# 301_PowerGridUSB.net
KiCad netlist of a schematic drawn in Altium Designer
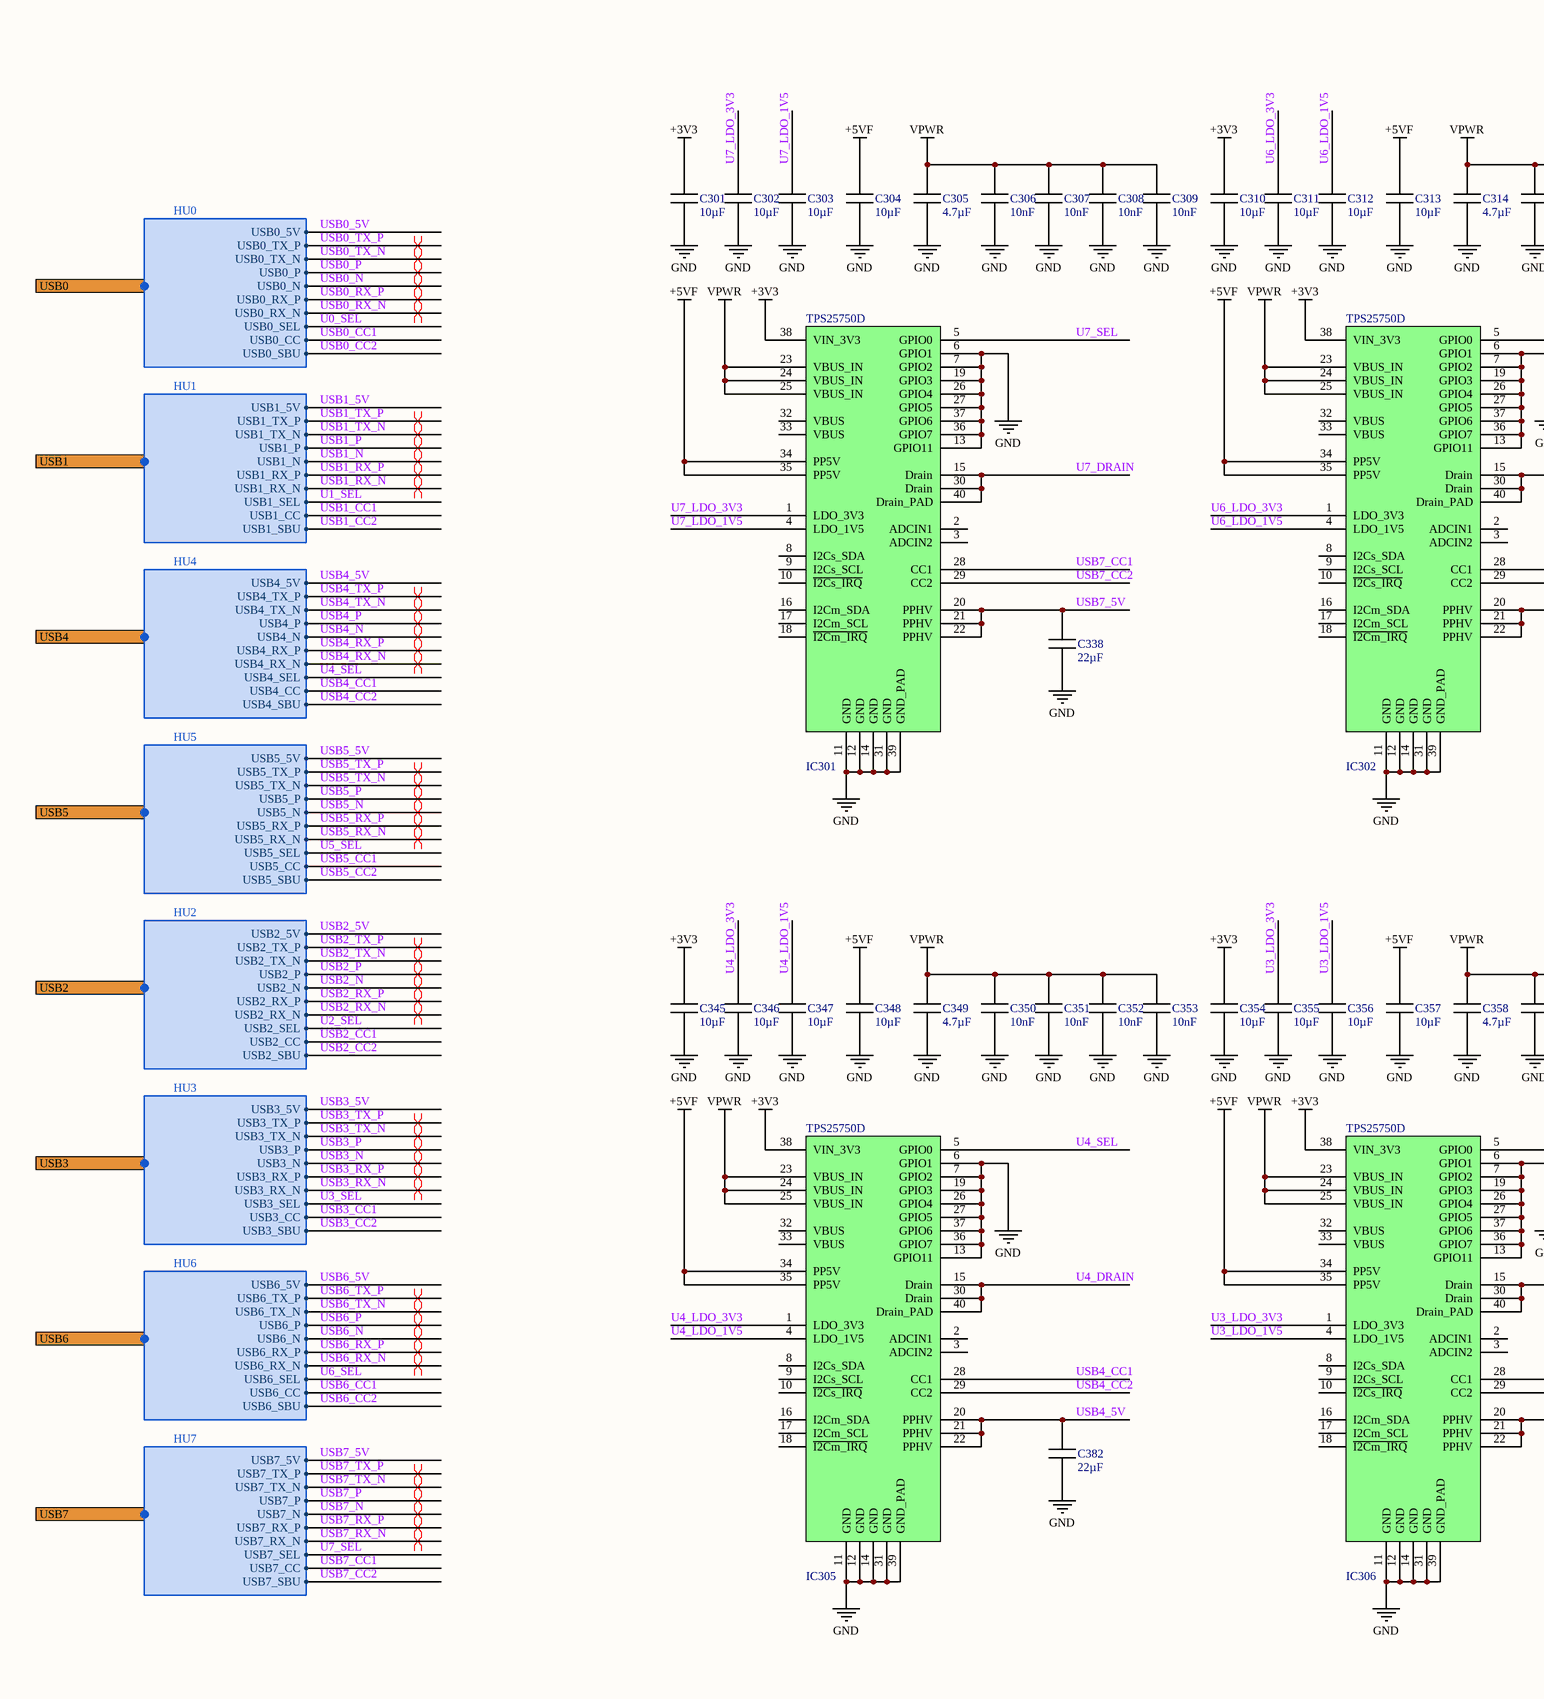
[diagram p0: 301_PowerGridUSB.SchDoc, left]
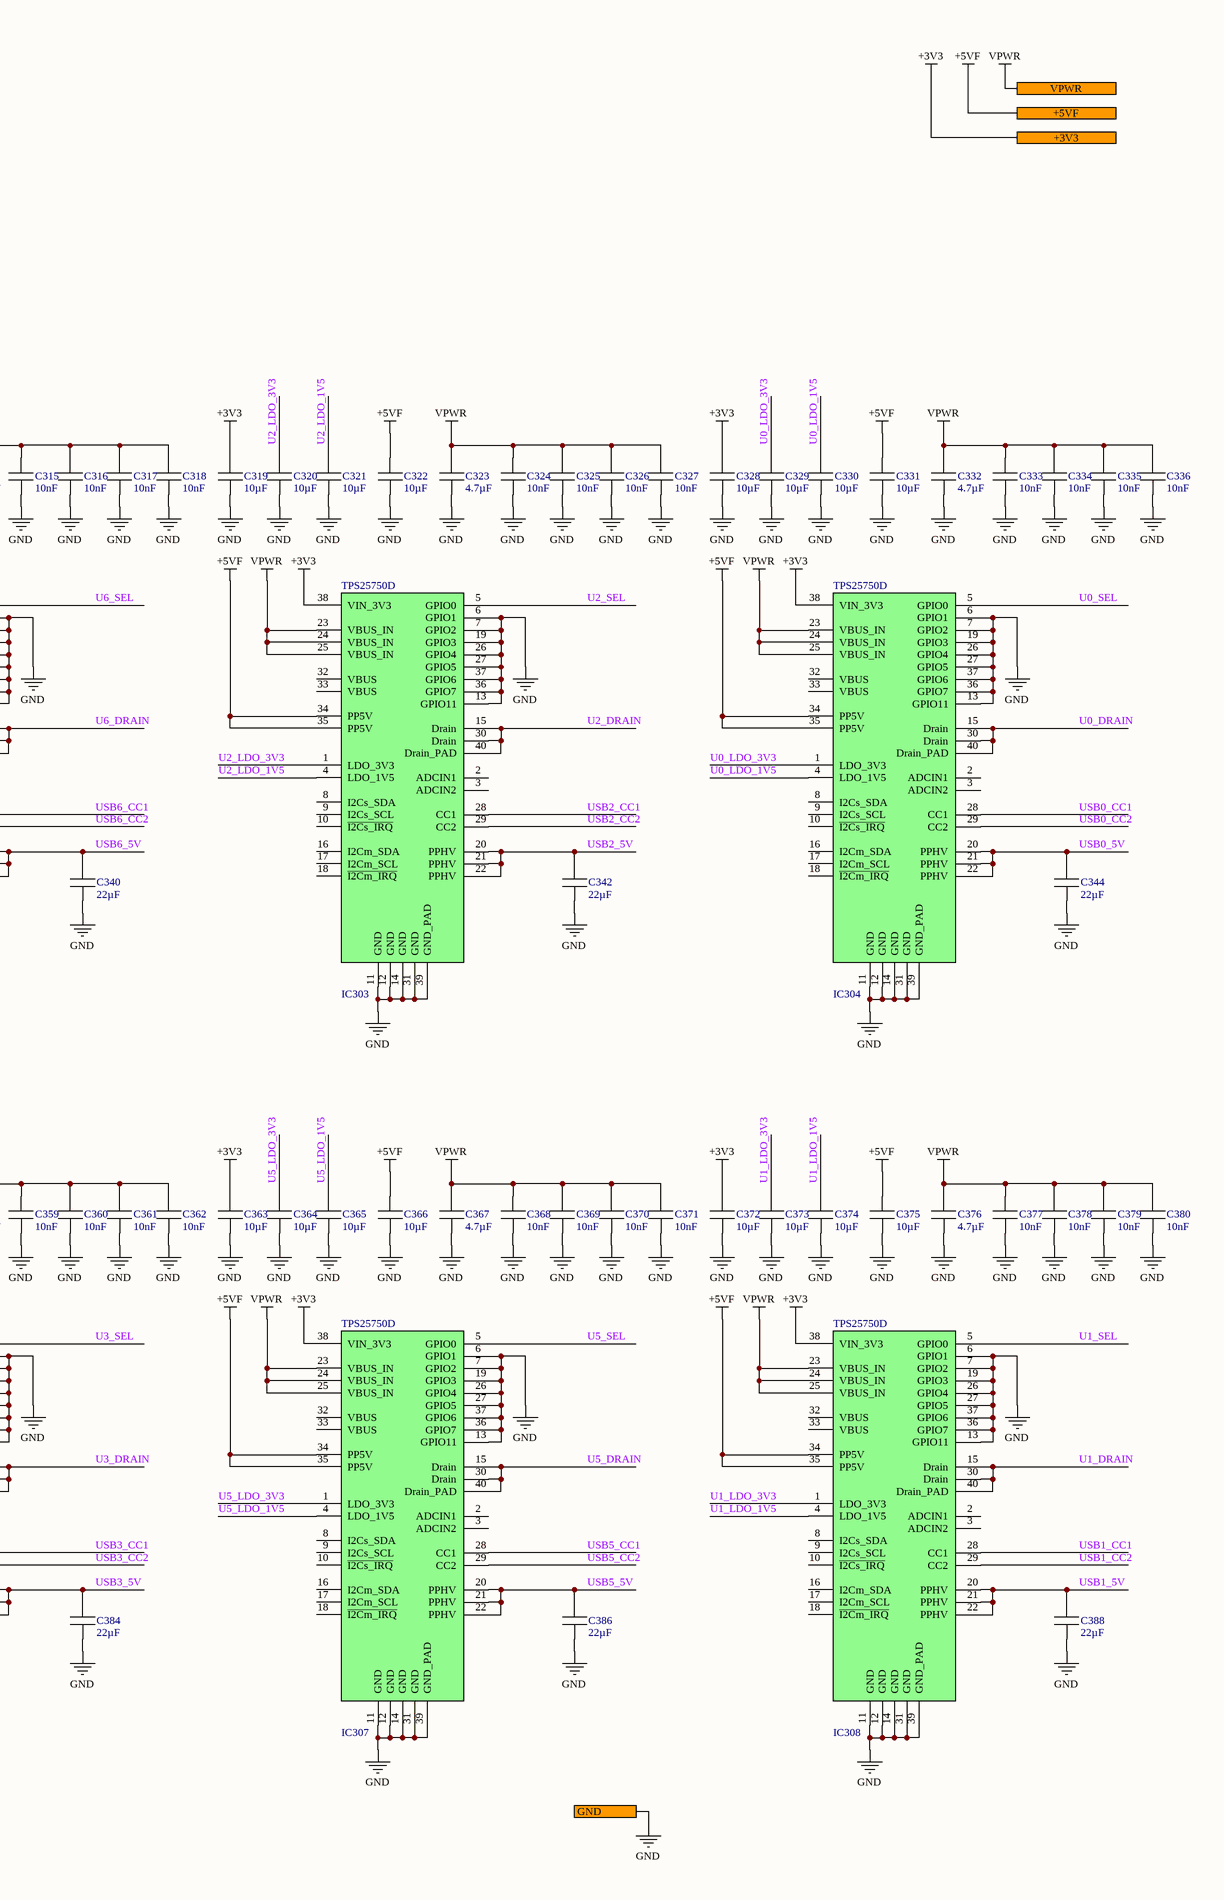
[diagram p1: 301_PowerGridUSB.SchDoc, right]

(export (version "E")
  (design (tool "Eeschema 10.0.6"))
  (components
    (comp (ref "C301")
      (value "10µF")
      (footprint "C0805")
      (description "10µF 16V 10% X5R")
      (fields
        (field (name "REFVAL") "10µF")
        (field (name "PART NUMBER") "CA0001")
        (field (name "MANFACTPART") "GRM21BR61C106KE15L")
      )
      (libsource (lib "GTS_Database") (part "C"))
    )
    (comp (ref "C302")
      (value "10µF")
      (footprint "C0805")
      (description "10µF 16V 10% X5R")
      (fields
        (field (name "REFVAL") "10µF")
        (field (name "PART NUMBER") "CA0001")
        (field (name "MANFACTPART") "GRM21BR61C106KE15L")
      )
      (libsource (lib "GTS_Database") (part "C"))
    )
    (comp (ref "C303")
      (value "10µF")
      (footprint "C0805")
      (description "10µF 16V 10% X5R")
      (fields
        (field (name "REFVAL") "10µF")
        (field (name "PART NUMBER") "CA0001")
        (field (name "MANFACTPART") "GRM21BR61C106KE15L")
      )
      (libsource (lib "GTS_Database") (part "C"))
    )
    (comp (ref "C304")
      (value "10µF")
      (footprint "C0805")
      (description "10µF 16V 10% X5R")
      (fields
        (field (name "REFVAL") "10µF")
        (field (name "PART NUMBER") "CA0001")
        (field (name "MANFACTPART") "GRM21BR61C106KE15L")
      )
      (libsource (lib "GTS_Database") (part "C"))
    )
    (comp (ref "C305")
      (value "4.7µF")
      (footprint "C1210")
      (description "4.7µF 100V 10% X5R")
      (fields
        (field (name "REFVAL") "4.7µF")
        (field (name "PART NUMBER") "CA0038")
        (field (name "MANFACTPART") "HMK325BJ475KM-PE")
      )
      (libsource (lib "GTS_Database") (part "C"))
    )
    (comp (ref "C306")
      (value "10nF")
      (footprint "C0805")
      (description "10nF 50V 10% X7R")
      (fields
        (field (name "REFVAL") "10nF")
        (field (name "PART NUMBER") "CA0021")
        (field (name "MANFACTPART") "C0805C103K5RAC")
      )
      (libsource (lib "GTS_Database") (part "C"))
    )
    (comp (ref "C307")
      (value "10nF")
      (footprint "C0805")
      (description "10nF 50V 10% X7R")
      (fields
        (field (name "REFVAL") "10nF")
        (field (name "PART NUMBER") "CA0021")
        (field (name "MANFACTPART") "C0805C103K5RAC")
      )
      (libsource (lib "GTS_Database") (part "C"))
    )
    (comp (ref "C308")
      (value "10nF")
      (footprint "C0805")
      (description "10nF 50V 10% X7R")
      (fields
        (field (name "REFVAL") "10nF")
        (field (name "PART NUMBER") "CA0021")
        (field (name "MANFACTPART") "C0805C103K5RAC")
      )
      (libsource (lib "GTS_Database") (part "C"))
    )
    (comp (ref "C309")
      (value "10nF")
      (footprint "C0805")
      (description "10nF 50V 10% X7R")
      (fields
        (field (name "REFVAL") "10nF")
        (field (name "PART NUMBER") "CA0021")
        (field (name "MANFACTPART") "C0805C103K5RAC")
      )
      (libsource (lib "GTS_Database") (part "C"))
    )
    (comp (ref "C310")
      (value "10µF")
      (footprint "C0805")
      (description "10µF 16V 10% X5R")
      (fields
        (field (name "REFVAL") "10µF")
        (field (name "PART NUMBER") "CA0001")
        (field (name "MANFACTPART") "GRM21BR61C106KE15L")
      )
      (libsource (lib "GTS_Database") (part "C"))
    )
    (comp (ref "C311")
      (value "10µF")
      (footprint "C0805")
      (description "10µF 16V 10% X5R")
      (fields
        (field (name "REFVAL") "10µF")
        (field (name "PART NUMBER") "CA0001")
        (field (name "MANFACTPART") "GRM21BR61C106KE15L")
      )
      (libsource (lib "GTS_Database") (part "C"))
    )
    (comp (ref "C312")
      (value "10µF")
      (footprint "C0805")
      (description "10µF 16V 10% X5R")
      (fields
        (field (name "REFVAL") "10µF")
        (field (name "PART NUMBER") "CA0001")
        (field (name "MANFACTPART") "GRM21BR61C106KE15L")
      )
      (libsource (lib "GTS_Database") (part "C"))
    )
    (comp (ref "C313")
      (value "10µF")
      (footprint "C0805")
      (description "10µF 16V 10% X5R")
      (fields
        (field (name "REFVAL") "10µF")
        (field (name "PART NUMBER") "CA0001")
        (field (name "MANFACTPART") "GRM21BR61C106KE15L")
      )
      (libsource (lib "GTS_Database") (part "C"))
    )
    (comp (ref "C314")
      (value "4.7µF")
      (footprint "C1210")
      (description "4.7µF 100V 10% X5R")
      (fields
        (field (name "REFVAL") "4.7µF")
        (field (name "PART NUMBER") "CA0038")
        (field (name "MANFACTPART") "HMK325BJ475KM-PE")
      )
      (libsource (lib "GTS_Database") (part "C"))
    )
    (comp (ref "C315")
      (value "10nF")
      (footprint "C0805")
      (description "10nF 50V 10% X7R")
      (fields
        (field (name "REFVAL") "10nF")
        (field (name "PART NUMBER") "CA0021")
        (field (name "MANFACTPART") "C0805C103K5RAC")
      )
      (libsource (lib "GTS_Database") (part "C"))
    )
    (comp (ref "C316")
      (value "10nF")
      (footprint "C0805")
      (description "10nF 50V 10% X7R")
      (fields
        (field (name "REFVAL") "10nF")
        (field (name "PART NUMBER") "CA0021")
        (field (name "MANFACTPART") "C0805C103K5RAC")
      )
      (libsource (lib "GTS_Database") (part "C"))
    )
    (comp (ref "C317")
      (value "10nF")
      (footprint "C0805")
      (description "10nF 50V 10% X7R")
      (fields
        (field (name "REFVAL") "10nF")
        (field (name "PART NUMBER") "CA0021")
        (field (name "MANFACTPART") "C0805C103K5RAC")
      )
      (libsource (lib "GTS_Database") (part "C"))
    )
    (comp (ref "C318")
      (value "10nF")
      (footprint "C0805")
      (description "10nF 50V 10% X7R")
      (fields
        (field (name "REFVAL") "10nF")
        (field (name "PART NUMBER") "CA0021")
        (field (name "MANFACTPART") "C0805C103K5RAC")
      )
      (libsource (lib "GTS_Database") (part "C"))
    )
    (comp (ref "C319")
      (value "10µF")
      (footprint "C0805")
      (description "10µF 16V 10% X5R")
      (fields
        (field (name "REFVAL") "10µF")
        (field (name "PART NUMBER") "CA0001")
        (field (name "MANFACTPART") "GRM21BR61C106KE15L")
      )
      (libsource (lib "GTS_Database") (part "C"))
    )
    (comp (ref "C320")
      (value "10µF")
      (footprint "C0805")
      (description "10µF 16V 10% X5R")
      (fields
        (field (name "REFVAL") "10µF")
        (field (name "PART NUMBER") "CA0001")
        (field (name "MANFACTPART") "GRM21BR61C106KE15L")
      )
      (libsource (lib "GTS_Database") (part "C"))
    )
    (comp (ref "C321")
      (value "10µF")
      (footprint "C0805")
      (description "10µF 16V 10% X5R")
      (fields
        (field (name "REFVAL") "10µF")
        (field (name "PART NUMBER") "CA0001")
        (field (name "MANFACTPART") "GRM21BR61C106KE15L")
      )
      (libsource (lib "GTS_Database") (part "C"))
    )
    (comp (ref "C322")
      (value "10µF")
      (footprint "C0805")
      (description "10µF 16V 10% X5R")
      (fields
        (field (name "REFVAL") "10µF")
        (field (name "PART NUMBER") "CA0001")
        (field (name "MANFACTPART") "GRM21BR61C106KE15L")
      )
      (libsource (lib "GTS_Database") (part "C"))
    )
    (comp (ref "C323")
      (value "4.7µF")
      (footprint "C1210")
      (description "4.7µF 100V 10% X5R")
      (fields
        (field (name "REFVAL") "4.7µF")
        (field (name "PART NUMBER") "CA0038")
        (field (name "MANFACTPART") "HMK325BJ475KM-PE")
      )
      (libsource (lib "GTS_Database") (part "C"))
    )
    (comp (ref "C324")
      (value "10nF")
      (footprint "C0805")
      (description "10nF 50V 10% X7R")
      (fields
        (field (name "REFVAL") "10nF")
        (field (name "PART NUMBER") "CA0021")
        (field (name "MANFACTPART") "C0805C103K5RAC")
      )
      (libsource (lib "GTS_Database") (part "C"))
    )
    (comp (ref "C325")
      (value "10nF")
      (footprint "C0805")
      (description "10nF 50V 10% X7R")
      (fields
        (field (name "REFVAL") "10nF")
        (field (name "PART NUMBER") "CA0021")
        (field (name "MANFACTPART") "C0805C103K5RAC")
      )
      (libsource (lib "GTS_Database") (part "C"))
    )
    (comp (ref "C326")
      (value "10nF")
      (footprint "C0805")
      (description "10nF 50V 10% X7R")
      (fields
        (field (name "REFVAL") "10nF")
        (field (name "PART NUMBER") "CA0021")
        (field (name "MANFACTPART") "C0805C103K5RAC")
      )
      (libsource (lib "GTS_Database") (part "C"))
    )
    (comp (ref "C327")
      (value "10nF")
      (footprint "C0805")
      (description "10nF 50V 10% X7R")
      (fields
        (field (name "REFVAL") "10nF")
        (field (name "PART NUMBER") "CA0021")
        (field (name "MANFACTPART") "C0805C103K5RAC")
      )
      (libsource (lib "GTS_Database") (part "C"))
    )
    (comp (ref "C328")
      (value "10µF")
      (footprint "C0805")
      (description "10µF 16V 10% X5R")
      (fields
        (field (name "REFVAL") "10µF")
        (field (name "PART NUMBER") "CA0001")
        (field (name "MANFACTPART") "GRM21BR61C106KE15L")
      )
      (libsource (lib "GTS_Database") (part "C"))
    )
    (comp (ref "C329")
      (value "10µF")
      (footprint "C0805")
      (description "10µF 16V 10% X5R")
      (fields
        (field (name "REFVAL") "10µF")
        (field (name "PART NUMBER") "CA0001")
        (field (name "MANFACTPART") "GRM21BR61C106KE15L")
      )
      (libsource (lib "GTS_Database") (part "C"))
    )
    (comp (ref "C330")
      (value "10µF")
      (footprint "C0805")
      (description "10µF 16V 10% X5R")
      (fields
        (field (name "REFVAL") "10µF")
        (field (name "PART NUMBER") "CA0001")
        (field (name "MANFACTPART") "GRM21BR61C106KE15L")
      )
      (libsource (lib "GTS_Database") (part "C"))
    )
    (comp (ref "C331")
      (value "10µF")
      (footprint "C0805")
      (description "10µF 16V 10% X5R")
      (fields
        (field (name "REFVAL") "10µF")
        (field (name "PART NUMBER") "CA0001")
        (field (name "MANFACTPART") "GRM21BR61C106KE15L")
      )
      (libsource (lib "GTS_Database") (part "C"))
    )
    (comp (ref "C332")
      (value "4.7µF")
      (footprint "C1210")
      (description "4.7µF 100V 10% X5R")
      (fields
        (field (name "REFVAL") "4.7µF")
        (field (name "PART NUMBER") "CA0038")
        (field (name "MANFACTPART") "HMK325BJ475KM-PE")
      )
      (libsource (lib "GTS_Database") (part "C"))
    )
    (comp (ref "C333")
      (value "10nF")
      (footprint "C0805")
      (description "10nF 50V 10% X7R")
      (fields
        (field (name "REFVAL") "10nF")
        (field (name "PART NUMBER") "CA0021")
        (field (name "MANFACTPART") "C0805C103K5RAC")
      )
      (libsource (lib "GTS_Database") (part "C"))
    )
    (comp (ref "C334")
      (value "10nF")
      (footprint "C0805")
      (description "10nF 50V 10% X7R")
      (fields
        (field (name "REFVAL") "10nF")
        (field (name "PART NUMBER") "CA0021")
        (field (name "MANFACTPART") "C0805C103K5RAC")
      )
      (libsource (lib "GTS_Database") (part "C"))
    )
    (comp (ref "C335")
      (value "10nF")
      (footprint "C0805")
      (description "10nF 50V 10% X7R")
      (fields
        (field (name "REFVAL") "10nF")
        (field (name "PART NUMBER") "CA0021")
        (field (name "MANFACTPART") "C0805C103K5RAC")
      )
      (libsource (lib "GTS_Database") (part "C"))
    )
    (comp (ref "C336")
      (value "10nF")
      (footprint "C0805")
      (description "10nF 50V 10% X7R")
      (fields
        (field (name "REFVAL") "10nF")
        (field (name "PART NUMBER") "CA0021")
        (field (name "MANFACTPART") "C0805C103K5RAC")
      )
      (libsource (lib "GTS_Database") (part "C"))
    )
    (comp (ref "C338")
      (value "22µF")
      (footprint "C2220")
      (description "22µF 63V 20% X7R")
      (fields
        (field (name "REFVAL") "22µF")
        (field (name "PART NUMBER") "CA0051")
        (field (name "MANFACTPART") "KRM55WR71J226MH01K")
      )
      (libsource (lib "GTS_Database") (part "C"))
    )
    (comp (ref "C340")
      (value "22µF")
      (footprint "C2220")
      (description "22µF 63V 20% X7R")
      (fields
        (field (name "REFVAL") "22µF")
        (field (name "PART NUMBER") "CA0051")
        (field (name "MANFACTPART") "KRM55WR71J226MH01K")
      )
      (libsource (lib "GTS_Database") (part "C"))
    )
    (comp (ref "C342")
      (value "22µF")
      (footprint "C2220")
      (description "22µF 63V 20% X7R")
      (fields
        (field (name "REFVAL") "22µF")
        (field (name "PART NUMBER") "CA0051")
        (field (name "MANFACTPART") "KRM55WR71J226MH01K")
      )
      (libsource (lib "GTS_Database") (part "C"))
    )
    (comp (ref "C344")
      (value "22µF")
      (footprint "C2220")
      (description "22µF 63V 20% X7R")
      (fields
        (field (name "REFVAL") "22µF")
        (field (name "PART NUMBER") "CA0051")
        (field (name "MANFACTPART") "KRM55WR71J226MH01K")
      )
      (libsource (lib "GTS_Database") (part "C"))
    )
    (comp (ref "C345")
      (value "10µF")
      (footprint "C0805")
      (description "10µF 16V 10% X5R")
      (fields
        (field (name "REFVAL") "10µF")
        (field (name "PART NUMBER") "CA0001")
        (field (name "MANFACTPART") "GRM21BR61C106KE15L")
      )
      (libsource (lib "GTS_Database") (part "C"))
    )
    (comp (ref "C346")
      (value "10µF")
      (footprint "C0805")
      (description "10µF 16V 10% X5R")
      (fields
        (field (name "REFVAL") "10µF")
        (field (name "PART NUMBER") "CA0001")
        (field (name "MANFACTPART") "GRM21BR61C106KE15L")
      )
      (libsource (lib "GTS_Database") (part "C"))
    )
    (comp (ref "C347")
      (value "10µF")
      (footprint "C0805")
      (description "10µF 16V 10% X5R")
      (fields
        (field (name "REFVAL") "10µF")
        (field (name "PART NUMBER") "CA0001")
        (field (name "MANFACTPART") "GRM21BR61C106KE15L")
      )
      (libsource (lib "GTS_Database") (part "C"))
    )
    (comp (ref "C348")
      (value "10µF")
      (footprint "C0805")
      (description "10µF 16V 10% X5R")
      (fields
        (field (name "REFVAL") "10µF")
        (field (name "PART NUMBER") "CA0001")
        (field (name "MANFACTPART") "GRM21BR61C106KE15L")
      )
      (libsource (lib "GTS_Database") (part "C"))
    )
    (comp (ref "C349")
      (value "4.7µF")
      (footprint "C1210")
      (description "4.7µF 100V 10% X5R")
      (fields
        (field (name "REFVAL") "4.7µF")
        (field (name "PART NUMBER") "CA0038")
        (field (name "MANFACTPART") "HMK325BJ475KM-PE")
      )
      (libsource (lib "GTS_Database") (part "C"))
    )
    (comp (ref "C350")
      (value "10nF")
      (footprint "C0805")
      (description "10nF 50V 10% X7R")
      (fields
        (field (name "REFVAL") "10nF")
        (field (name "PART NUMBER") "CA0021")
        (field (name "MANFACTPART") "C0805C103K5RAC")
      )
      (libsource (lib "GTS_Database") (part "C"))
    )
    (comp (ref "C351")
      (value "10nF")
      (footprint "C0805")
      (description "10nF 50V 10% X7R")
      (fields
        (field (name "REFVAL") "10nF")
        (field (name "PART NUMBER") "CA0021")
        (field (name "MANFACTPART") "C0805C103K5RAC")
      )
      (libsource (lib "GTS_Database") (part "C"))
    )
    (comp (ref "C352")
      (value "10nF")
      (footprint "C0805")
      (description "10nF 50V 10% X7R")
      (fields
        (field (name "REFVAL") "10nF")
        (field (name "PART NUMBER") "CA0021")
        (field (name "MANFACTPART") "C0805C103K5RAC")
      )
      (libsource (lib "GTS_Database") (part "C"))
    )
    (comp (ref "C353")
      (value "10nF")
      (footprint "C0805")
      (description "10nF 50V 10% X7R")
      (fields
        (field (name "REFVAL") "10nF")
        (field (name "PART NUMBER") "CA0021")
        (field (name "MANFACTPART") "C0805C103K5RAC")
      )
      (libsource (lib "GTS_Database") (part "C"))
    )
    (comp (ref "C354")
      (value "10µF")
      (footprint "C0805")
      (description "10µF 16V 10% X5R")
      (fields
        (field (name "REFVAL") "10µF")
        (field (name "PART NUMBER") "CA0001")
        (field (name "MANFACTPART") "GRM21BR61C106KE15L")
      )
      (libsource (lib "GTS_Database") (part "C"))
    )
    (comp (ref "C355")
      (value "10µF")
      (footprint "C0805")
      (description "10µF 16V 10% X5R")
      (fields
        (field (name "REFVAL") "10µF")
        (field (name "PART NUMBER") "CA0001")
        (field (name "MANFACTPART") "GRM21BR61C106KE15L")
      )
      (libsource (lib "GTS_Database") (part "C"))
    )
    (comp (ref "C356")
      (value "10µF")
      (footprint "C0805")
      (description "10µF 16V 10% X5R")
      (fields
        (field (name "REFVAL") "10µF")
        (field (name "PART NUMBER") "CA0001")
        (field (name "MANFACTPART") "GRM21BR61C106KE15L")
      )
      (libsource (lib "GTS_Database") (part "C"))
    )
    (comp (ref "C357")
      (value "10µF")
      (footprint "C0805")
      (description "10µF 16V 10% X5R")
      (fields
        (field (name "REFVAL") "10µF")
        (field (name "PART NUMBER") "CA0001")
        (field (name "MANFACTPART") "GRM21BR61C106KE15L")
      )
      (libsource (lib "GTS_Database") (part "C"))
    )
    (comp (ref "C358")
      (value "4.7µF")
      (footprint "C1210")
      (description "4.7µF 100V 10% X5R")
      (fields
        (field (name "REFVAL") "4.7µF")
        (field (name "PART NUMBER") "CA0038")
        (field (name "MANFACTPART") "HMK325BJ475KM-PE")
      )
      (libsource (lib "GTS_Database") (part "C"))
    )
    (comp (ref "C359")
      (value "10nF")
      (footprint "C0805")
      (description "10nF 50V 10% X7R")
      (fields
        (field (name "REFVAL") "10nF")
        (field (name "PART NUMBER") "CA0021")
        (field (name "MANFACTPART") "C0805C103K5RAC")
      )
      (libsource (lib "GTS_Database") (part "C"))
    )
    (comp (ref "C360")
      (value "10nF")
      (footprint "C0805")
      (description "10nF 50V 10% X7R")
      (fields
        (field (name "REFVAL") "10nF")
        (field (name "PART NUMBER") "CA0021")
        (field (name "MANFACTPART") "C0805C103K5RAC")
      )
      (libsource (lib "GTS_Database") (part "C"))
    )
    (comp (ref "C361")
      (value "10nF")
      (footprint "C0805")
      (description "10nF 50V 10% X7R")
      (fields
        (field (name "REFVAL") "10nF")
        (field (name "PART NUMBER") "CA0021")
        (field (name "MANFACTPART") "C0805C103K5RAC")
      )
      (libsource (lib "GTS_Database") (part "C"))
    )
    (comp (ref "C362")
      (value "10nF")
      (footprint "C0805")
      (description "10nF 50V 10% X7R")
      (fields
        (field (name "REFVAL") "10nF")
        (field (name "PART NUMBER") "CA0021")
        (field (name "MANFACTPART") "C0805C103K5RAC")
      )
      (libsource (lib "GTS_Database") (part "C"))
    )
    (comp (ref "C363")
      (value "10µF")
      (footprint "C0805")
      (description "10µF 16V 10% X5R")
      (fields
        (field (name "REFVAL") "10µF")
        (field (name "PART NUMBER") "CA0001")
        (field (name "MANFACTPART") "GRM21BR61C106KE15L")
      )
      (libsource (lib "GTS_Database") (part "C"))
    )
    (comp (ref "C364")
      (value "10µF")
      (footprint "C0805")
      (description "10µF 16V 10% X5R")
      (fields
        (field (name "REFVAL") "10µF")
        (field (name "PART NUMBER") "CA0001")
        (field (name "MANFACTPART") "GRM21BR61C106KE15L")
      )
      (libsource (lib "GTS_Database") (part "C"))
    )
    (comp (ref "C365")
      (value "10µF")
      (footprint "C0805")
      (description "10µF 16V 10% X5R")
      (fields
        (field (name "REFVAL") "10µF")
        (field (name "PART NUMBER") "CA0001")
        (field (name "MANFACTPART") "GRM21BR61C106KE15L")
      )
      (libsource (lib "GTS_Database") (part "C"))
    )
    (comp (ref "C366")
      (value "10µF")
      (footprint "C0805")
      (description "10µF 16V 10% X5R")
      (fields
        (field (name "REFVAL") "10µF")
        (field (name "PART NUMBER") "CA0001")
        (field (name "MANFACTPART") "GRM21BR61C106KE15L")
      )
      (libsource (lib "GTS_Database") (part "C"))
    )
    (comp (ref "C367")
      (value "4.7µF")
      (footprint "C1210")
      (description "4.7µF 100V 10% X5R")
      (fields
        (field (name "REFVAL") "4.7µF")
        (field (name "PART NUMBER") "CA0038")
        (field (name "MANFACTPART") "HMK325BJ475KM-PE")
      )
      (libsource (lib "GTS_Database") (part "C"))
    )
    (comp (ref "C368")
      (value "10nF")
      (footprint "C0805")
      (description "10nF 50V 10% X7R")
      (fields
        (field (name "REFVAL") "10nF")
        (field (name "PART NUMBER") "CA0021")
        (field (name "MANFACTPART") "C0805C103K5RAC")
      )
      (libsource (lib "GTS_Database") (part "C"))
    )
    (comp (ref "C369")
      (value "10nF")
      (footprint "C0805")
      (description "10nF 50V 10% X7R")
      (fields
        (field (name "REFVAL") "10nF")
        (field (name "PART NUMBER") "CA0021")
        (field (name "MANFACTPART") "C0805C103K5RAC")
      )
      (libsource (lib "GTS_Database") (part "C"))
    )
    (comp (ref "C370")
      (value "10nF")
      (footprint "C0805")
      (description "10nF 50V 10% X7R")
      (fields
        (field (name "REFVAL") "10nF")
        (field (name "PART NUMBER") "CA0021")
        (field (name "MANFACTPART") "C0805C103K5RAC")
      )
      (libsource (lib "GTS_Database") (part "C"))
    )
    (comp (ref "C371")
      (value "10nF")
      (footprint "C0805")
      (description "10nF 50V 10% X7R")
      (fields
        (field (name "REFVAL") "10nF")
        (field (name "PART NUMBER") "CA0021")
        (field (name "MANFACTPART") "C0805C103K5RAC")
      )
      (libsource (lib "GTS_Database") (part "C"))
    )
    (comp (ref "C372")
      (value "10µF")
      (footprint "C0805")
      (description "10µF 16V 10% X5R")
      (fields
        (field (name "REFVAL") "10µF")
        (field (name "PART NUMBER") "CA0001")
        (field (name "MANFACTPART") "GRM21BR61C106KE15L")
      )
      (libsource (lib "GTS_Database") (part "C"))
    )
    (comp (ref "C373")
      (value "10µF")
      (footprint "C0805")
      (description "10µF 16V 10% X5R")
      (fields
        (field (name "REFVAL") "10µF")
        (field (name "PART NUMBER") "CA0001")
        (field (name "MANFACTPART") "GRM21BR61C106KE15L")
      )
      (libsource (lib "GTS_Database") (part "C"))
    )
    (comp (ref "C374")
      (value "10µF")
      (footprint "C0805")
      (description "10µF 16V 10% X5R")
      (fields
        (field (name "REFVAL") "10µF")
        (field (name "PART NUMBER") "CA0001")
        (field (name "MANFACTPART") "GRM21BR61C106KE15L")
      )
      (libsource (lib "GTS_Database") (part "C"))
    )
    (comp (ref "C375")
      (value "10µF")
      (footprint "C0805")
      (description "10µF 16V 10% X5R")
      (fields
        (field (name "REFVAL") "10µF")
        (field (name "PART NUMBER") "CA0001")
        (field (name "MANFACTPART") "GRM21BR61C106KE15L")
      )
      (libsource (lib "GTS_Database") (part "C"))
    )
    (comp (ref "C376")
      (value "4.7µF")
      (footprint "C1210")
      (description "4.7µF 100V 10% X5R")
      (fields
        (field (name "REFVAL") "4.7µF")
        (field (name "PART NUMBER") "CA0038")
        (field (name "MANFACTPART") "HMK325BJ475KM-PE")
      )
      (libsource (lib "GTS_Database") (part "C"))
    )
    (comp (ref "C377")
      (value "10nF")
      (footprint "C0805")
      (description "10nF 50V 10% X7R")
      (fields
        (field (name "REFVAL") "10nF")
        (field (name "PART NUMBER") "CA0021")
        (field (name "MANFACTPART") "C0805C103K5RAC")
      )
      (libsource (lib "GTS_Database") (part "C"))
    )
    (comp (ref "C378")
      (value "10nF")
      (footprint "C0805")
      (description "10nF 50V 10% X7R")
      (fields
        (field (name "REFVAL") "10nF")
        (field (name "PART NUMBER") "CA0021")
        (field (name "MANFACTPART") "C0805C103K5RAC")
      )
      (libsource (lib "GTS_Database") (part "C"))
    )
    (comp (ref "C379")
      (value "10nF")
      (footprint "C0805")
      (description "10nF 50V 10% X7R")
      (fields
        (field (name "REFVAL") "10nF")
        (field (name "PART NUMBER") "CA0021")
        (field (name "MANFACTPART") "C0805C103K5RAC")
      )
      (libsource (lib "GTS_Database") (part "C"))
    )
    (comp (ref "C380")
      (value "10nF")
      (footprint "C0805")
      (description "10nF 50V 10% X7R")
      (fields
        (field (name "REFVAL") "10nF")
        (field (name "PART NUMBER") "CA0021")
        (field (name "MANFACTPART") "C0805C103K5RAC")
      )
      (libsource (lib "GTS_Database") (part "C"))
    )
    (comp (ref "C382")
      (value "22µF")
      (footprint "C2220")
      (description "22µF 63V 20% X7R")
      (fields
        (field (name "REFVAL") "22µF")
        (field (name "PART NUMBER") "CA0051")
        (field (name "MANFACTPART") "KRM55WR71J226MH01K")
      )
      (libsource (lib "GTS_Database") (part "C"))
    )
    (comp (ref "C384")
      (value "22µF")
      (footprint "C2220")
      (description "22µF 63V 20% X7R")
      (fields
        (field (name "REFVAL") "22µF")
        (field (name "PART NUMBER") "CA0051")
        (field (name "MANFACTPART") "KRM55WR71J226MH01K")
      )
      (libsource (lib "GTS_Database") (part "C"))
    )
    (comp (ref "C386")
      (value "22µF")
      (footprint "C2220")
      (description "22µF 63V 20% X7R")
      (fields
        (field (name "REFVAL") "22µF")
        (field (name "PART NUMBER") "CA0051")
        (field (name "MANFACTPART") "KRM55WR71J226MH01K")
      )
      (libsource (lib "GTS_Database") (part "C"))
    )
    (comp (ref "C388")
      (value "22µF")
      (footprint "C2220")
      (description "22µF 63V 20% X7R")
      (fields
        (field (name "REFVAL") "22µF")
        (field (name "PART NUMBER") "CA0051")
        (field (name "MANFACTPART") "KRM55WR71J226MH01K")
      )
      (libsource (lib "GTS_Database") (part "C"))
    )
    (comp (ref "IC301")
      (value "TPS25750D")
      (footprint "QFNRJK-38")
      (description "USB Type-C and USB PD Controller with Integrated Power Switches Optimized for Power Applications")
      (fields (field (name "REFVAL") "TPS25750D") (field (name "PART NUMBER") "IC0041"))
      (libsource (lib "GTS_Database") (part "TPS25750D"))
    )
    (comp (ref "IC302")
      (value "TPS25750D")
      (footprint "QFNRJK-38")
      (description "USB Type-C and USB PD Controller with Integrated Power Switches Optimized for Power Applications")
      (fields (field (name "REFVAL") "TPS25750D") (field (name "PART NUMBER") "IC0041"))
      (libsource (lib "GTS_Database") (part "TPS25750D"))
    )
    (comp (ref "IC303")
      (value "TPS25750D")
      (footprint "QFNRJK-38")
      (description "USB Type-C and USB PD Controller with Integrated Power Switches Optimized for Power Applications")
      (fields (field (name "REFVAL") "TPS25750D") (field (name "PART NUMBER") "IC0041"))
      (libsource (lib "GTS_Database") (part "TPS25750D"))
    )
    (comp (ref "IC304")
      (value "TPS25750D")
      (footprint "QFNRJK-38")
      (description "USB Type-C and USB PD Controller with Integrated Power Switches Optimized for Power Applications")
      (fields (field (name "REFVAL") "TPS25750D") (field (name "PART NUMBER") "IC0041"))
      (libsource (lib "GTS_Database") (part "TPS25750D"))
    )
    (comp (ref "IC305")
      (value "TPS25750D")
      (footprint "QFNRJK-38")
      (description "USB Type-C and USB PD Controller with Integrated Power Switches Optimized for Power Applications")
      (fields (field (name "REFVAL") "TPS25750D") (field (name "PART NUMBER") "IC0041"))
      (libsource (lib "GTS_Database") (part "TPS25750D"))
    )
    (comp (ref "IC306")
      (value "TPS25750D")
      (footprint "QFNRJK-38")
      (description "USB Type-C and USB PD Controller with Integrated Power Switches Optimized for Power Applications")
      (fields (field (name "REFVAL") "TPS25750D") (field (name "PART NUMBER") "IC0041"))
      (libsource (lib "GTS_Database") (part "TPS25750D"))
    )
    (comp (ref "IC307")
      (value "TPS25750D")
      (footprint "QFNRJK-38")
      (description "USB Type-C and USB PD Controller with Integrated Power Switches Optimized for Power Applications")
      (fields (field (name "REFVAL") "TPS25750D") (field (name "PART NUMBER") "IC0041"))
      (libsource (lib "GTS_Database") (part "TPS25750D"))
    )
    (comp (ref "IC308")
      (value "TPS25750D")
      (footprint "QFNRJK-38")
      (description "USB Type-C and USB PD Controller with Integrated Power Switches Optimized for Power Applications")
      (fields (field (name "REFVAL") "TPS25750D") (field (name "PART NUMBER") "IC0041"))
      (libsource (lib "GTS_Database") (part "TPS25750D"))
    )
  )
  (nets
    (net (code "9") (name "+3V3") (class "Default")
      (node (ref "C301") (pin "1") (pinfunction "1_1") (pintype "passive"))
      (node (ref "C310") (pin "1") (pinfunction "1_1") (pintype "passive"))
      (node (ref "C319") (pin "1") (pinfunction "1_1") (pintype "passive"))
      (node (ref "C328") (pin "1") (pinfunction "1_1") (pintype "passive"))
      (node (ref "C345") (pin "1") (pinfunction "1_1") (pintype "passive"))
      (node (ref "C354") (pin "1") (pinfunction "1_1") (pintype "passive"))
      (node (ref "C363") (pin "1") (pinfunction "1_1") (pintype "passive"))
      (node (ref "C372") (pin "1") (pinfunction "1_1") (pintype "passive"))
      (node (ref "IC301") (pin "38") (pinfunction "VIN_3V3_38") (pintype "passive"))
      (node (ref "IC302") (pin "38") (pinfunction "VIN_3V3_38") (pintype "passive"))
      (node (ref "IC303") (pin "38") (pinfunction "VIN_3V3_38") (pintype "passive"))
      (node (ref "IC304") (pin "38") (pinfunction "VIN_3V3_38") (pintype "passive"))
      (node (ref "IC305") (pin "38") (pinfunction "VIN_3V3_38") (pintype "passive"))
      (node (ref "IC306") (pin "38") (pinfunction "VIN_3V3_38") (pintype "passive"))
      (node (ref "IC307") (pin "38") (pinfunction "VIN_3V3_38") (pintype "passive"))
      (node (ref "IC308") (pin "38") (pinfunction "VIN_3V3_38") (pintype "passive"))
    )
    (net (code "10") (name "+5VF") (class "Default")
      (node (ref "C304") (pin "1") (pinfunction "1_1") (pintype "passive"))
      (node (ref "C313") (pin "1") (pinfunction "1_1") (pintype "passive"))
      (node (ref "C322") (pin "1") (pinfunction "1_1") (pintype "passive"))
      (node (ref "C331") (pin "1") (pinfunction "1_1") (pintype "passive"))
      (node (ref "C348") (pin "1") (pinfunction "1_1") (pintype "passive"))
      (node (ref "C357") (pin "1") (pinfunction "1_1") (pintype "passive"))
      (node (ref "C366") (pin "1") (pinfunction "1_1") (pintype "passive"))
      (node (ref "C375") (pin "1") (pinfunction "1_1") (pintype "passive"))
      (node (ref "IC301") (pin "34") (pinfunction "PP5V_34") (pintype "passive"))
      (node (ref "IC301") (pin "35") (pinfunction "PP5V_35") (pintype "passive"))
      (node (ref "IC302") (pin "34") (pinfunction "PP5V_34") (pintype "passive"))
      (node (ref "IC302") (pin "35") (pinfunction "PP5V_35") (pintype "passive"))
      (node (ref "IC303") (pin "34") (pinfunction "PP5V_34") (pintype "passive"))
      (node (ref "IC303") (pin "35") (pinfunction "PP5V_35") (pintype "passive"))
      (node (ref "IC304") (pin "34") (pinfunction "PP5V_34") (pintype "passive"))
      (node (ref "IC304") (pin "35") (pinfunction "PP5V_35") (pintype "passive"))
      (node (ref "IC305") (pin "34") (pinfunction "PP5V_34") (pintype "passive"))
      (node (ref "IC305") (pin "35") (pinfunction "PP5V_35") (pintype "passive"))
      (node (ref "IC306") (pin "34") (pinfunction "PP5V_34") (pintype "passive"))
      (node (ref "IC306") (pin "35") (pinfunction "PP5V_35") (pintype "passive"))
      (node (ref "IC307") (pin "34") (pinfunction "PP5V_34") (pintype "passive"))
      (node (ref "IC307") (pin "35") (pinfunction "PP5V_35") (pintype "passive"))
      (node (ref "IC308") (pin "34") (pinfunction "PP5V_34") (pintype "passive"))
      (node (ref "IC308") (pin "35") (pinfunction "PP5V_35") (pintype "passive"))
    )
    (net (code "11") (name "/U0_DRAIN") (class "Default")
      (node (ref "IC304") (pin "15") (pinfunction "Drain_15") (pintype "passive"))
      (node (ref "IC304") (pin "30") (pinfunction "Drain_30") (pintype "passive"))
      (node (ref "IC304") (pin "40") (pinfunction "Drain_PAD_40") (pintype "passive"))
    )
    (net (code "12") (name "/U0_LDO_1V5") (class "Default")
      (node (ref "C330") (pin "1") (pinfunction "1_1") (pintype "passive"))
      (node (ref "IC304") (pin "4") (pinfunction "LDO_1V5_4") (pintype "passive"))
    )
    (net (code "13") (name "/U0_LDO_3V3") (class "Default")
      (node (ref "C329") (pin "1") (pinfunction "1_1") (pintype "passive"))
      (node (ref "IC304") (pin "1") (pinfunction "LDO_3V3_1") (pintype "passive"))
    )
    (net (code "14") (name "/U0_SEL") (class "Default")
      (node (ref "IC304") (pin "5") (pinfunction "GPIO0_5") (pintype "passive"))
    )
    (net (code "15") (name "/U1_DRAIN") (class "Default")
      (node (ref "IC308") (pin "15") (pinfunction "Drain_15") (pintype "passive"))
      (node (ref "IC308") (pin "30") (pinfunction "Drain_30") (pintype "passive"))
      (node (ref "IC308") (pin "40") (pinfunction "Drain_PAD_40") (pintype "passive"))
    )
    (net (code "16") (name "/U1_LDO_1V5") (class "Default")
      (node (ref "C374") (pin "1") (pinfunction "1_1") (pintype "passive"))
      (node (ref "IC308") (pin "4") (pinfunction "LDO_1V5_4") (pintype "passive"))
    )
    (net (code "17") (name "/U1_LDO_3V3") (class "Default")
      (node (ref "C373") (pin "1") (pinfunction "1_1") (pintype "passive"))
      (node (ref "IC308") (pin "1") (pinfunction "LDO_3V3_1") (pintype "passive"))
    )
    (net (code "18") (name "/U1_SEL") (class "Default")
      (node (ref "IC308") (pin "5") (pinfunction "GPIO0_5") (pintype "passive"))
    )
    (net (code "19") (name "/U2_DRAIN") (class "Default")
      (node (ref "IC303") (pin "15") (pinfunction "Drain_15") (pintype "passive"))
      (node (ref "IC303") (pin "30") (pinfunction "Drain_30") (pintype "passive"))
      (node (ref "IC303") (pin "40") (pinfunction "Drain_PAD_40") (pintype "passive"))
    )
    (net (code "20") (name "/U2_LDO_1V5") (class "Default")
      (node (ref "C321") (pin "1") (pinfunction "1_1") (pintype "passive"))
      (node (ref "IC303") (pin "4") (pinfunction "LDO_1V5_4") (pintype "passive"))
    )
    (net (code "21") (name "/U2_LDO_3V3") (class "Default")
      (node (ref "C320") (pin "1") (pinfunction "1_1") (pintype "passive"))
      (node (ref "IC303") (pin "1") (pinfunction "LDO_3V3_1") (pintype "passive"))
    )
    (net (code "22") (name "/U2_SEL") (class "Default")
      (node (ref "IC303") (pin "5") (pinfunction "GPIO0_5") (pintype "passive"))
    )
    (net (code "23") (name "/U3_DRAIN") (class "Default")
      (node (ref "IC306") (pin "15") (pinfunction "Drain_15") (pintype "passive"))
      (node (ref "IC306") (pin "30") (pinfunction "Drain_30") (pintype "passive"))
      (node (ref "IC306") (pin "40") (pinfunction "Drain_PAD_40") (pintype "passive"))
    )
    (net (code "24") (name "/U3_LDO_1V5") (class "Default")
      (node (ref "C356") (pin "1") (pinfunction "1_1") (pintype "passive"))
      (node (ref "IC306") (pin "4") (pinfunction "LDO_1V5_4") (pintype "passive"))
    )
    (net (code "25") (name "/U3_LDO_3V3") (class "Default")
      (node (ref "C355") (pin "1") (pinfunction "1_1") (pintype "passive"))
      (node (ref "IC306") (pin "1") (pinfunction "LDO_3V3_1") (pintype "passive"))
    )
    (net (code "26") (name "/U3_SEL") (class "Default")
      (node (ref "IC306") (pin "5") (pinfunction "GPIO0_5") (pintype "passive"))
    )
    (net (code "27") (name "/U4_DRAIN") (class "Default")
      (node (ref "IC305") (pin "15") (pinfunction "Drain_15") (pintype "passive"))
      (node (ref "IC305") (pin "30") (pinfunction "Drain_30") (pintype "passive"))
      (node (ref "IC305") (pin "40") (pinfunction "Drain_PAD_40") (pintype "passive"))
    )
    (net (code "28") (name "/U4_LDO_1V5") (class "Default")
      (node (ref "C347") (pin "1") (pinfunction "1_1") (pintype "passive"))
      (node (ref "IC305") (pin "4") (pinfunction "LDO_1V5_4") (pintype "passive"))
    )
    (net (code "29") (name "/U4_LDO_3V3") (class "Default")
      (node (ref "C346") (pin "1") (pinfunction "1_1") (pintype "passive"))
      (node (ref "IC305") (pin "1") (pinfunction "LDO_3V3_1") (pintype "passive"))
    )
    (net (code "30") (name "/U4_SEL") (class "Default")
      (node (ref "IC305") (pin "5") (pinfunction "GPIO0_5") (pintype "passive"))
    )
    (net (code "31") (name "/U5_DRAIN") (class "Default")
      (node (ref "IC307") (pin "15") (pinfunction "Drain_15") (pintype "passive"))
      (node (ref "IC307") (pin "30") (pinfunction "Drain_30") (pintype "passive"))
      (node (ref "IC307") (pin "40") (pinfunction "Drain_PAD_40") (pintype "passive"))
    )
    (net (code "32") (name "/U5_LDO_1V5") (class "Default")
      (node (ref "C365") (pin "1") (pinfunction "1_1") (pintype "passive"))
      (node (ref "IC307") (pin "4") (pinfunction "LDO_1V5_4") (pintype "passive"))
    )
    (net (code "33") (name "/U5_LDO_3V3") (class "Default")
      (node (ref "C364") (pin "1") (pinfunction "1_1") (pintype "passive"))
      (node (ref "IC307") (pin "1") (pinfunction "LDO_3V3_1") (pintype "passive"))
    )
    (net (code "34") (name "/U5_SEL") (class "Default")
      (node (ref "IC307") (pin "5") (pinfunction "GPIO0_5") (pintype "passive"))
    )
    (net (code "35") (name "/U6_DRAIN") (class "Default")
      (node (ref "IC302") (pin "15") (pinfunction "Drain_15") (pintype "passive"))
      (node (ref "IC302") (pin "30") (pinfunction "Drain_30") (pintype "passive"))
      (node (ref "IC302") (pin "40") (pinfunction "Drain_PAD_40") (pintype "passive"))
    )
    (net (code "36") (name "/U6_LDO_1V5") (class "Default")
      (node (ref "C312") (pin "1") (pinfunction "1_1") (pintype "passive"))
      (node (ref "IC302") (pin "4") (pinfunction "LDO_1V5_4") (pintype "passive"))
    )
    (net (code "37") (name "/U6_LDO_3V3") (class "Default")
      (node (ref "C311") (pin "1") (pinfunction "1_1") (pintype "passive"))
      (node (ref "IC302") (pin "1") (pinfunction "LDO_3V3_1") (pintype "passive"))
    )
    (net (code "38") (name "/U6_SEL") (class "Default")
      (node (ref "IC302") (pin "5") (pinfunction "GPIO0_5") (pintype "passive"))
    )
    (net (code "39") (name "/U7_DRAIN") (class "Default")
      (node (ref "IC301") (pin "15") (pinfunction "Drain_15") (pintype "passive"))
      (node (ref "IC301") (pin "30") (pinfunction "Drain_30") (pintype "passive"))
      (node (ref "IC301") (pin "40") (pinfunction "Drain_PAD_40") (pintype "passive"))
    )
    (net (code "40") (name "/U7_LDO_1V5") (class "Default")
      (node (ref "C303") (pin "1") (pinfunction "1_1") (pintype "passive"))
      (node (ref "IC301") (pin "4") (pinfunction "LDO_1V5_4") (pintype "passive"))
    )
    (net (code "41") (name "/U7_LDO_3V3") (class "Default")
      (node (ref "C302") (pin "1") (pinfunction "1_1") (pintype "passive"))
      (node (ref "IC301") (pin "1") (pinfunction "LDO_3V3_1") (pintype "passive"))
    )
    (net (code "42") (name "/U7_SEL") (class "Default")
      (node (ref "IC301") (pin "5") (pinfunction "GPIO0_5") (pintype "passive"))
    )
    (net (code "43") (name "/USB0_5V") (class "Default")
      (node (ref "C344") (pin "1") (pinfunction "1_1") (pintype "passive"))
      (node (ref "IC304") (pin "20") (pinfunction "PPHV_20") (pintype "passive"))
      (node (ref "IC304") (pin "21") (pinfunction "PPHV_21") (pintype "passive"))
      (node (ref "IC304") (pin "22") (pinfunction "PPHV_22") (pintype "passive"))
    )
    (net (code "44") (name "/USB0_CC1") (class "Default")
      (node (ref "IC304") (pin "28") (pinfunction "CC1_28") (pintype "passive"))
    )
    (net (code "45") (name "/USB0_CC2") (class "Default")
      (node (ref "IC304") (pin "29") (pinfunction "CC2_29") (pintype "passive"))
    )
    (net (code "52") (name "/USB1_5V") (class "Default")
      (node (ref "C388") (pin "1") (pinfunction "1_1") (pintype "passive"))
      (node (ref "IC308") (pin "20") (pinfunction "PPHV_20") (pintype "passive"))
      (node (ref "IC308") (pin "21") (pinfunction "PPHV_21") (pintype "passive"))
      (node (ref "IC308") (pin "22") (pinfunction "PPHV_22") (pintype "passive"))
    )
    (net (code "53") (name "/USB1_CC1") (class "Default")
      (node (ref "IC308") (pin "28") (pinfunction "CC1_28") (pintype "passive"))
    )
    (net (code "54") (name "/USB1_CC2") (class "Default")
      (node (ref "IC308") (pin "29") (pinfunction "CC2_29") (pintype "passive"))
    )
    (net (code "61") (name "/USB2_5V") (class "Default")
      (node (ref "C342") (pin "1") (pinfunction "1_1") (pintype "passive"))
      (node (ref "IC303") (pin "20") (pinfunction "PPHV_20") (pintype "passive"))
      (node (ref "IC303") (pin "21") (pinfunction "PPHV_21") (pintype "passive"))
      (node (ref "IC303") (pin "22") (pinfunction "PPHV_22") (pintype "passive"))
    )
    (net (code "62") (name "/USB2_CC1") (class "Default")
      (node (ref "IC303") (pin "28") (pinfunction "CC1_28") (pintype "passive"))
    )
    (net (code "63") (name "/USB2_CC2") (class "Default")
      (node (ref "IC303") (pin "29") (pinfunction "CC2_29") (pintype "passive"))
    )
    (net (code "70") (name "/USB3_5V") (class "Default")
      (node (ref "C384") (pin "1") (pinfunction "1_1") (pintype "passive"))
      (node (ref "IC306") (pin "20") (pinfunction "PPHV_20") (pintype "passive"))
      (node (ref "IC306") (pin "21") (pinfunction "PPHV_21") (pintype "passive"))
      (node (ref "IC306") (pin "22") (pinfunction "PPHV_22") (pintype "passive"))
    )
    (net (code "71") (name "/USB3_CC1") (class "Default")
      (node (ref "IC306") (pin "28") (pinfunction "CC1_28") (pintype "passive"))
    )
    (net (code "72") (name "/USB3_CC2") (class "Default")
      (node (ref "IC306") (pin "29") (pinfunction "CC2_29") (pintype "passive"))
    )
    (net (code "79") (name "/USB4_5V") (class "Default")
      (node (ref "C382") (pin "1") (pinfunction "1_1") (pintype "passive"))
      (node (ref "IC305") (pin "20") (pinfunction "PPHV_20") (pintype "passive"))
      (node (ref "IC305") (pin "21") (pinfunction "PPHV_21") (pintype "passive"))
      (node (ref "IC305") (pin "22") (pinfunction "PPHV_22") (pintype "passive"))
    )
    (net (code "80") (name "/USB4_CC1") (class "Default")
      (node (ref "IC305") (pin "28") (pinfunction "CC1_28") (pintype "passive"))
    )
    (net (code "81") (name "/USB4_CC2") (class "Default")
      (node (ref "IC305") (pin "29") (pinfunction "CC2_29") (pintype "passive"))
    )
    (net (code "88") (name "/USB5_5V") (class "Default")
      (node (ref "C386") (pin "1") (pinfunction "1_1") (pintype "passive"))
      (node (ref "IC307") (pin "20") (pinfunction "PPHV_20") (pintype "passive"))
      (node (ref "IC307") (pin "21") (pinfunction "PPHV_21") (pintype "passive"))
      (node (ref "IC307") (pin "22") (pinfunction "PPHV_22") (pintype "passive"))
    )
    (net (code "89") (name "/USB5_CC1") (class "Default")
      (node (ref "IC307") (pin "28") (pinfunction "CC1_28") (pintype "passive"))
    )
    (net (code "90") (name "/USB5_CC2") (class "Default")
      (node (ref "IC307") (pin "29") (pinfunction "CC2_29") (pintype "passive"))
    )
    (net (code "97") (name "/USB6_5V") (class "Default")
      (node (ref "C340") (pin "1") (pinfunction "1_1") (pintype "passive"))
      (node (ref "IC302") (pin "20") (pinfunction "PPHV_20") (pintype "passive"))
      (node (ref "IC302") (pin "21") (pinfunction "PPHV_21") (pintype "passive"))
      (node (ref "IC302") (pin "22") (pinfunction "PPHV_22") (pintype "passive"))
    )
    (net (code "98") (name "/USB6_CC1") (class "Default")
      (node (ref "IC302") (pin "28") (pinfunction "CC1_28") (pintype "passive"))
    )
    (net (code "99") (name "/USB6_CC2") (class "Default")
      (node (ref "IC302") (pin "29") (pinfunction "CC2_29") (pintype "passive"))
    )
    (net (code "106") (name "/USB7_5V") (class "Default")
      (node (ref "C338") (pin "1") (pinfunction "1_1") (pintype "passive"))
      (node (ref "IC301") (pin "20") (pinfunction "PPHV_20") (pintype "passive"))
      (node (ref "IC301") (pin "21") (pinfunction "PPHV_21") (pintype "passive"))
      (node (ref "IC301") (pin "22") (pinfunction "PPHV_22") (pintype "passive"))
    )
    (net (code "107") (name "/USB7_CC1") (class "Default")
      (node (ref "IC301") (pin "28") (pinfunction "CC1_28") (pintype "passive"))
    )
    (net (code "108") (name "/USB7_CC2") (class "Default")
      (node (ref "IC301") (pin "29") (pinfunction "CC2_29") (pintype "passive"))
    )
    (net (code "123") (name "GND") (class "Default")
      (node (ref "C301") (pin "2") (pinfunction "2_2") (pintype "passive"))
      (node (ref "C302") (pin "2") (pinfunction "2_2") (pintype "passive"))
      (node (ref "C303") (pin "2") (pinfunction "2_2") (pintype "passive"))
      (node (ref "C304") (pin "2") (pinfunction "2_2") (pintype "passive"))
      (node (ref "C305") (pin "2") (pinfunction "2_2") (pintype "passive"))
      (node (ref "C306") (pin "2") (pinfunction "2_2") (pintype "passive"))
      (node (ref "C307") (pin "2") (pinfunction "2_2") (pintype "passive"))
      (node (ref "C308") (pin "2") (pinfunction "2_2") (pintype "passive"))
      (node (ref "C309") (pin "2") (pinfunction "2_2") (pintype "passive"))
      (node (ref "C310") (pin "2") (pinfunction "2_2") (pintype "passive"))
      (node (ref "C311") (pin "2") (pinfunction "2_2") (pintype "passive"))
      (node (ref "C312") (pin "2") (pinfunction "2_2") (pintype "passive"))
      (node (ref "C313") (pin "2") (pinfunction "2_2") (pintype "passive"))
      (node (ref "C314") (pin "2") (pinfunction "2_2") (pintype "passive"))
      (node (ref "C315") (pin "2") (pinfunction "2_2") (pintype "passive"))
      (node (ref "C316") (pin "2") (pinfunction "2_2") (pintype "passive"))
      (node (ref "C317") (pin "2") (pinfunction "2_2") (pintype "passive"))
      (node (ref "C318") (pin "2") (pinfunction "2_2") (pintype "passive"))
      (node (ref "C319") (pin "2") (pinfunction "2_2") (pintype "passive"))
      (node (ref "C320") (pin "2") (pinfunction "2_2") (pintype "passive"))
      (node (ref "C321") (pin "2") (pinfunction "2_2") (pintype "passive"))
      (node (ref "C322") (pin "2") (pinfunction "2_2") (pintype "passive"))
      (node (ref "C323") (pin "2") (pinfunction "2_2") (pintype "passive"))
      (node (ref "C324") (pin "2") (pinfunction "2_2") (pintype "passive"))
      (node (ref "C325") (pin "2") (pinfunction "2_2") (pintype "passive"))
      (node (ref "C326") (pin "2") (pinfunction "2_2") (pintype "passive"))
      (node (ref "C327") (pin "2") (pinfunction "2_2") (pintype "passive"))
      (node (ref "C328") (pin "2") (pinfunction "2_2") (pintype "passive"))
      (node (ref "C329") (pin "2") (pinfunction "2_2") (pintype "passive"))
      (node (ref "C330") (pin "2") (pinfunction "2_2") (pintype "passive"))
      (node (ref "C331") (pin "2") (pinfunction "2_2") (pintype "passive"))
      (node (ref "C332") (pin "2") (pinfunction "2_2") (pintype "passive"))
      (node (ref "C333") (pin "2") (pinfunction "2_2") (pintype "passive"))
      (node (ref "C334") (pin "2") (pinfunction "2_2") (pintype "passive"))
      (node (ref "C335") (pin "2") (pinfunction "2_2") (pintype "passive"))
      (node (ref "C336") (pin "2") (pinfunction "2_2") (pintype "passive"))
      (node (ref "C338") (pin "2") (pinfunction "2_2") (pintype "passive"))
      (node (ref "C340") (pin "2") (pinfunction "2_2") (pintype "passive"))
      (node (ref "C342") (pin "2") (pinfunction "2_2") (pintype "passive"))
      (node (ref "C344") (pin "2") (pinfunction "2_2") (pintype "passive"))
      (node (ref "C345") (pin "2") (pinfunction "2_2") (pintype "passive"))
      (node (ref "C346") (pin "2") (pinfunction "2_2") (pintype "passive"))
      (node (ref "C347") (pin "2") (pinfunction "2_2") (pintype "passive"))
      (node (ref "C348") (pin "2") (pinfunction "2_2") (pintype "passive"))
      (node (ref "C349") (pin "2") (pinfunction "2_2") (pintype "passive"))
      (node (ref "C350") (pin "2") (pinfunction "2_2") (pintype "passive"))
      (node (ref "C351") (pin "2") (pinfunction "2_2") (pintype "passive"))
      (node (ref "C352") (pin "2") (pinfunction "2_2") (pintype "passive"))
      (node (ref "C353") (pin "2") (pinfunction "2_2") (pintype "passive"))
      (node (ref "C354") (pin "2") (pinfunction "2_2") (pintype "passive"))
      (node (ref "C355") (pin "2") (pinfunction "2_2") (pintype "passive"))
      (node (ref "C356") (pin "2") (pinfunction "2_2") (pintype "passive"))
      (node (ref "C357") (pin "2") (pinfunction "2_2") (pintype "passive"))
      (node (ref "C358") (pin "2") (pinfunction "2_2") (pintype "passive"))
      (node (ref "C359") (pin "2") (pinfunction "2_2") (pintype "passive"))
      (node (ref "C360") (pin "2") (pinfunction "2_2") (pintype "passive"))
      (node (ref "C361") (pin "2") (pinfunction "2_2") (pintype "passive"))
      (node (ref "C362") (pin "2") (pinfunction "2_2") (pintype "passive"))
      (node (ref "C363") (pin "2") (pinfunction "2_2") (pintype "passive"))
      (node (ref "C364") (pin "2") (pinfunction "2_2") (pintype "passive"))
      (node (ref "C365") (pin "2") (pinfunction "2_2") (pintype "passive"))
      (node (ref "C366") (pin "2") (pinfunction "2_2") (pintype "passive"))
      (node (ref "C367") (pin "2") (pinfunction "2_2") (pintype "passive"))
      (node (ref "C368") (pin "2") (pinfunction "2_2") (pintype "passive"))
      (node (ref "C369") (pin "2") (pinfunction "2_2") (pintype "passive"))
      (node (ref "C370") (pin "2") (pinfunction "2_2") (pintype "passive"))
      (node (ref "C371") (pin "2") (pinfunction "2_2") (pintype "passive"))
      (node (ref "C372") (pin "2") (pinfunction "2_2") (pintype "passive"))
      (node (ref "C373") (pin "2") (pinfunction "2_2") (pintype "passive"))
      (node (ref "C374") (pin "2") (pinfunction "2_2") (pintype "passive"))
      (node (ref "C375") (pin "2") (pinfunction "2_2") (pintype "passive"))
      (node (ref "C376") (pin "2") (pinfunction "2_2") (pintype "passive"))
      (node (ref "C377") (pin "2") (pinfunction "2_2") (pintype "passive"))
      (node (ref "C378") (pin "2") (pinfunction "2_2") (pintype "passive"))
      (node (ref "C379") (pin "2") (pinfunction "2_2") (pintype "passive"))
      (node (ref "C380") (pin "2") (pinfunction "2_2") (pintype "passive"))
      (node (ref "C382") (pin "2") (pinfunction "2_2") (pintype "passive"))
      (node (ref "C384") (pin "2") (pinfunction "2_2") (pintype "passive"))
      (node (ref "C386") (pin "2") (pinfunction "2_2") (pintype "passive"))
      (node (ref "C388") (pin "2") (pinfunction "2_2") (pintype "passive"))
      (node (ref "IC301") (pin "11") (pinfunction "GND_11") (pintype "passive"))
      (node (ref "IC301") (pin "12") (pinfunction "GND_12") (pintype "passive"))
      (node (ref "IC301") (pin "13") (pinfunction "GPIO11_13") (pintype "passive"))
      (node (ref "IC301") (pin "14") (pinfunction "GND_14") (pintype "passive"))
      (node (ref "IC301") (pin "19") (pinfunction "GPIO3_19") (pintype "passive"))
      (node (ref "IC301") (pin "26") (pinfunction "GPIO4_26") (pintype "passive"))
      (node (ref "IC301") (pin "27") (pinfunction "GPIO5_27") (pintype "passive"))
      (node (ref "IC301") (pin "31") (pinfunction "GND_31") (pintype "passive"))
      (node (ref "IC301") (pin "36") (pinfunction "GPIO7_36") (pintype "passive"))
      (node (ref "IC301") (pin "37") (pinfunction "GPIO6_37") (pintype "passive"))
      (node (ref "IC301") (pin "39") (pinfunction "GND_PAD_39") (pintype "passive"))
      (node (ref "IC301") (pin "6") (pinfunction "GPIO1_6") (pintype "passive"))
      (node (ref "IC301") (pin "7") (pinfunction "GPIO2_7") (pintype "passive"))
      (node (ref "IC302") (pin "11") (pinfunction "GND_11") (pintype "passive"))
      (node (ref "IC302") (pin "12") (pinfunction "GND_12") (pintype "passive"))
      (node (ref "IC302") (pin "13") (pinfunction "GPIO11_13") (pintype "passive"))
      (node (ref "IC302") (pin "14") (pinfunction "GND_14") (pintype "passive"))
      (node (ref "IC302") (pin "19") (pinfunction "GPIO3_19") (pintype "passive"))
      (node (ref "IC302") (pin "26") (pinfunction "GPIO4_26") (pintype "passive"))
      (node (ref "IC302") (pin "27") (pinfunction "GPIO5_27") (pintype "passive"))
      (node (ref "IC302") (pin "31") (pinfunction "GND_31") (pintype "passive"))
      (node (ref "IC302") (pin "36") (pinfunction "GPIO7_36") (pintype "passive"))
      (node (ref "IC302") (pin "37") (pinfunction "GPIO6_37") (pintype "passive"))
      (node (ref "IC302") (pin "39") (pinfunction "GND_PAD_39") (pintype "passive"))
      (node (ref "IC302") (pin "6") (pinfunction "GPIO1_6") (pintype "passive"))
      (node (ref "IC302") (pin "7") (pinfunction "GPIO2_7") (pintype "passive"))
      (node (ref "IC303") (pin "11") (pinfunction "GND_11") (pintype "passive"))
      (node (ref "IC303") (pin "12") (pinfunction "GND_12") (pintype "passive"))
      (node (ref "IC303") (pin "13") (pinfunction "GPIO11_13") (pintype "passive"))
      (node (ref "IC303") (pin "14") (pinfunction "GND_14") (pintype "passive"))
      (node (ref "IC303") (pin "19") (pinfunction "GPIO3_19") (pintype "passive"))
      (node (ref "IC303") (pin "26") (pinfunction "GPIO4_26") (pintype "passive"))
      (node (ref "IC303") (pin "27") (pinfunction "GPIO5_27") (pintype "passive"))
      (node (ref "IC303") (pin "31") (pinfunction "GND_31") (pintype "passive"))
      (node (ref "IC303") (pin "36") (pinfunction "GPIO7_36") (pintype "passive"))
      (node (ref "IC303") (pin "37") (pinfunction "GPIO6_37") (pintype "passive"))
      (node (ref "IC303") (pin "39") (pinfunction "GND_PAD_39") (pintype "passive"))
      (node (ref "IC303") (pin "6") (pinfunction "GPIO1_6") (pintype "passive"))
      (node (ref "IC303") (pin "7") (pinfunction "GPIO2_7") (pintype "passive"))
      (node (ref "IC304") (pin "11") (pinfunction "GND_11") (pintype "passive"))
      (node (ref "IC304") (pin "12") (pinfunction "GND_12") (pintype "passive"))
      (node (ref "IC304") (pin "13") (pinfunction "GPIO11_13") (pintype "passive"))
      (node (ref "IC304") (pin "14") (pinfunction "GND_14") (pintype "passive"))
      (node (ref "IC304") (pin "19") (pinfunction "GPIO3_19") (pintype "passive"))
      (node (ref "IC304") (pin "26") (pinfunction "GPIO4_26") (pintype "passive"))
      (node (ref "IC304") (pin "27") (pinfunction "GPIO5_27") (pintype "passive"))
      (node (ref "IC304") (pin "31") (pinfunction "GND_31") (pintype "passive"))
      (node (ref "IC304") (pin "36") (pinfunction "GPIO7_36") (pintype "passive"))
      (node (ref "IC304") (pin "37") (pinfunction "GPIO6_37") (pintype "passive"))
      (node (ref "IC304") (pin "39") (pinfunction "GND_PAD_39") (pintype "passive"))
      (node (ref "IC304") (pin "6") (pinfunction "GPIO1_6") (pintype "passive"))
      (node (ref "IC304") (pin "7") (pinfunction "GPIO2_7") (pintype "passive"))
      (node (ref "IC305") (pin "11") (pinfunction "GND_11") (pintype "passive"))
      (node (ref "IC305") (pin "12") (pinfunction "GND_12") (pintype "passive"))
      (node (ref "IC305") (pin "13") (pinfunction "GPIO11_13") (pintype "passive"))
      (node (ref "IC305") (pin "14") (pinfunction "GND_14") (pintype "passive"))
      (node (ref "IC305") (pin "19") (pinfunction "GPIO3_19") (pintype "passive"))
      (node (ref "IC305") (pin "26") (pinfunction "GPIO4_26") (pintype "passive"))
      (node (ref "IC305") (pin "27") (pinfunction "GPIO5_27") (pintype "passive"))
      (node (ref "IC305") (pin "31") (pinfunction "GND_31") (pintype "passive"))
      (node (ref "IC305") (pin "36") (pinfunction "GPIO7_36") (pintype "passive"))
      (node (ref "IC305") (pin "37") (pinfunction "GPIO6_37") (pintype "passive"))
      (node (ref "IC305") (pin "39") (pinfunction "GND_PAD_39") (pintype "passive"))
      (node (ref "IC305") (pin "6") (pinfunction "GPIO1_6") (pintype "passive"))
      (node (ref "IC305") (pin "7") (pinfunction "GPIO2_7") (pintype "passive"))
      (node (ref "IC306") (pin "11") (pinfunction "GND_11") (pintype "passive"))
      (node (ref "IC306") (pin "12") (pinfunction "GND_12") (pintype "passive"))
      (node (ref "IC306") (pin "13") (pinfunction "GPIO11_13") (pintype "passive"))
      (node (ref "IC306") (pin "14") (pinfunction "GND_14") (pintype "passive"))
      (node (ref "IC306") (pin "19") (pinfunction "GPIO3_19") (pintype "passive"))
      (node (ref "IC306") (pin "26") (pinfunction "GPIO4_26") (pintype "passive"))
      (node (ref "IC306") (pin "27") (pinfunction "GPIO5_27") (pintype "passive"))
      (node (ref "IC306") (pin "31") (pinfunction "GND_31") (pintype "passive"))
      (node (ref "IC306") (pin "36") (pinfunction "GPIO7_36") (pintype "passive"))
      (node (ref "IC306") (pin "37") (pinfunction "GPIO6_37") (pintype "passive"))
      (node (ref "IC306") (pin "39") (pinfunction "GND_PAD_39") (pintype "passive"))
      (node (ref "IC306") (pin "6") (pinfunction "GPIO1_6") (pintype "passive"))
      (node (ref "IC306") (pin "7") (pinfunction "GPIO2_7") (pintype "passive"))
      (node (ref "IC307") (pin "11") (pinfunction "GND_11") (pintype "passive"))
      (node (ref "IC307") (pin "12") (pinfunction "GND_12") (pintype "passive"))
      (node (ref "IC307") (pin "13") (pinfunction "GPIO11_13") (pintype "passive"))
      (node (ref "IC307") (pin "14") (pinfunction "GND_14") (pintype "passive"))
      (node (ref "IC307") (pin "19") (pinfunction "GPIO3_19") (pintype "passive"))
      (node (ref "IC307") (pin "26") (pinfunction "GPIO4_26") (pintype "passive"))
      (node (ref "IC307") (pin "27") (pinfunction "GPIO5_27") (pintype "passive"))
      (node (ref "IC307") (pin "31") (pinfunction "GND_31") (pintype "passive"))
      (node (ref "IC307") (pin "36") (pinfunction "GPIO7_36") (pintype "passive"))
      (node (ref "IC307") (pin "37") (pinfunction "GPIO6_37") (pintype "passive"))
      (node (ref "IC307") (pin "39") (pinfunction "GND_PAD_39") (pintype "passive"))
      (node (ref "IC307") (pin "6") (pinfunction "GPIO1_6") (pintype "passive"))
      (node (ref "IC307") (pin "7") (pinfunction "GPIO2_7") (pintype "passive"))
      (node (ref "IC308") (pin "11") (pinfunction "GND_11") (pintype "passive"))
      (node (ref "IC308") (pin "12") (pinfunction "GND_12") (pintype "passive"))
      (node (ref "IC308") (pin "13") (pinfunction "GPIO11_13") (pintype "passive"))
      (node (ref "IC308") (pin "14") (pinfunction "GND_14") (pintype "passive"))
      (node (ref "IC308") (pin "19") (pinfunction "GPIO3_19") (pintype "passive"))
      (node (ref "IC308") (pin "26") (pinfunction "GPIO4_26") (pintype "passive"))
      (node (ref "IC308") (pin "27") (pinfunction "GPIO5_27") (pintype "passive"))
      (node (ref "IC308") (pin "31") (pinfunction "GND_31") (pintype "passive"))
      (node (ref "IC308") (pin "36") (pinfunction "GPIO7_36") (pintype "passive"))
      (node (ref "IC308") (pin "37") (pinfunction "GPIO6_37") (pintype "passive"))
      (node (ref "IC308") (pin "39") (pinfunction "GND_PAD_39") (pintype "passive"))
      (node (ref "IC308") (pin "6") (pinfunction "GPIO1_6") (pintype "passive"))
      (node (ref "IC308") (pin "7") (pinfunction "GPIO2_7") (pintype "passive"))
    )
    (net (code "124") (name "VPWR") (class "Default")
      (node (ref "C305") (pin "1") (pinfunction "1_1") (pintype "passive"))
      (node (ref "C306") (pin "1") (pinfunction "1_1") (pintype "passive"))
      (node (ref "C307") (pin "1") (pinfunction "1_1") (pintype "passive"))
      (node (ref "C308") (pin "1") (pinfunction "1_1") (pintype "passive"))
      (node (ref "C309") (pin "1") (pinfunction "1_1") (pintype "passive"))
      (node (ref "C314") (pin "1") (pinfunction "1_1") (pintype "passive"))
      (node (ref "C315") (pin "1") (pinfunction "1_1") (pintype "passive"))
      (node (ref "C316") (pin "1") (pinfunction "1_1") (pintype "passive"))
      (node (ref "C317") (pin "1") (pinfunction "1_1") (pintype "passive"))
      (node (ref "C318") (pin "1") (pinfunction "1_1") (pintype "passive"))
      (node (ref "C323") (pin "1") (pinfunction "1_1") (pintype "passive"))
      (node (ref "C324") (pin "1") (pinfunction "1_1") (pintype "passive"))
      (node (ref "C325") (pin "1") (pinfunction "1_1") (pintype "passive"))
      (node (ref "C326") (pin "1") (pinfunction "1_1") (pintype "passive"))
      (node (ref "C327") (pin "1") (pinfunction "1_1") (pintype "passive"))
      (node (ref "C332") (pin "1") (pinfunction "1_1") (pintype "passive"))
      (node (ref "C333") (pin "1") (pinfunction "1_1") (pintype "passive"))
      (node (ref "C334") (pin "1") (pinfunction "1_1") (pintype "passive"))
      (node (ref "C335") (pin "1") (pinfunction "1_1") (pintype "passive"))
      (node (ref "C336") (pin "1") (pinfunction "1_1") (pintype "passive"))
      (node (ref "C349") (pin "1") (pinfunction "1_1") (pintype "passive"))
      (node (ref "C350") (pin "1") (pinfunction "1_1") (pintype "passive"))
      (node (ref "C351") (pin "1") (pinfunction "1_1") (pintype "passive"))
      (node (ref "C352") (pin "1") (pinfunction "1_1") (pintype "passive"))
      (node (ref "C353") (pin "1") (pinfunction "1_1") (pintype "passive"))
      (node (ref "C358") (pin "1") (pinfunction "1_1") (pintype "passive"))
      (node (ref "C359") (pin "1") (pinfunction "1_1") (pintype "passive"))
      (node (ref "C360") (pin "1") (pinfunction "1_1") (pintype "passive"))
      (node (ref "C361") (pin "1") (pinfunction "1_1") (pintype "passive"))
      (node (ref "C362") (pin "1") (pinfunction "1_1") (pintype "passive"))
      (node (ref "C367") (pin "1") (pinfunction "1_1") (pintype "passive"))
      (node (ref "C368") (pin "1") (pinfunction "1_1") (pintype "passive"))
      (node (ref "C369") (pin "1") (pinfunction "1_1") (pintype "passive"))
      (node (ref "C370") (pin "1") (pinfunction "1_1") (pintype "passive"))
      (node (ref "C371") (pin "1") (pinfunction "1_1") (pintype "passive"))
      (node (ref "C376") (pin "1") (pinfunction "1_1") (pintype "passive"))
      (node (ref "C377") (pin "1") (pinfunction "1_1") (pintype "passive"))
      (node (ref "C378") (pin "1") (pinfunction "1_1") (pintype "passive"))
      (node (ref "C379") (pin "1") (pinfunction "1_1") (pintype "passive"))
      (node (ref "C380") (pin "1") (pinfunction "1_1") (pintype "passive"))
      (node (ref "IC301") (pin "23") (pinfunction "VBUS_IN_23") (pintype "passive"))
      (node (ref "IC301") (pin "24") (pinfunction "VBUS_IN_24") (pintype "passive"))
      (node (ref "IC301") (pin "25") (pinfunction "VBUS_IN_25") (pintype "passive"))
      (node (ref "IC302") (pin "23") (pinfunction "VBUS_IN_23") (pintype "passive"))
      (node (ref "IC302") (pin "24") (pinfunction "VBUS_IN_24") (pintype "passive"))
      (node (ref "IC302") (pin "25") (pinfunction "VBUS_IN_25") (pintype "passive"))
      (node (ref "IC303") (pin "23") (pinfunction "VBUS_IN_23") (pintype "passive"))
      (node (ref "IC303") (pin "24") (pinfunction "VBUS_IN_24") (pintype "passive"))
      (node (ref "IC303") (pin "25") (pinfunction "VBUS_IN_25") (pintype "passive"))
      (node (ref "IC304") (pin "23") (pinfunction "VBUS_IN_23") (pintype "passive"))
      (node (ref "IC304") (pin "24") (pinfunction "VBUS_IN_24") (pintype "passive"))
      (node (ref "IC304") (pin "25") (pinfunction "VBUS_IN_25") (pintype "passive"))
      (node (ref "IC305") (pin "23") (pinfunction "VBUS_IN_23") (pintype "passive"))
      (node (ref "IC305") (pin "24") (pinfunction "VBUS_IN_24") (pintype "passive"))
      (node (ref "IC305") (pin "25") (pinfunction "VBUS_IN_25") (pintype "passive"))
      (node (ref "IC306") (pin "23") (pinfunction "VBUS_IN_23") (pintype "passive"))
      (node (ref "IC306") (pin "24") (pinfunction "VBUS_IN_24") (pintype "passive"))
      (node (ref "IC306") (pin "25") (pinfunction "VBUS_IN_25") (pintype "passive"))
      (node (ref "IC307") (pin "23") (pinfunction "VBUS_IN_23") (pintype "passive"))
      (node (ref "IC307") (pin "24") (pinfunction "VBUS_IN_24") (pintype "passive"))
      (node (ref "IC307") (pin "25") (pinfunction "VBUS_IN_25") (pintype "passive"))
      (node (ref "IC308") (pin "23") (pinfunction "VBUS_IN_23") (pintype "passive"))
      (node (ref "IC308") (pin "24") (pinfunction "VBUS_IN_24") (pintype "passive"))
      (node (ref "IC308") (pin "25") (pinfunction "VBUS_IN_25") (pintype "passive"))
    )
    (net (code "125") (name "unconnected-(IC301-ADCIN1-Pad2)") (class "Default")
      (node (ref "IC301") (pin "2") (pinfunction "ADCIN1_2") (pintype "passive"))
    )
    (net (code "126") (name "unconnected-(IC301-ADCIN2-Pad3)") (class "Default")
      (node (ref "IC301") (pin "3") (pinfunction "ADCIN2_3") (pintype "passive"))
    )
    (net (code "127") (name "unconnected-(IC301-I2Cm_IRQ-Pad18)") (class "Default")
      (node (ref "IC301") (pin "18") (pinfunction "I2Cm_IRQ_18") (pintype "passive"))
    )
    (net (code "128") (name "unconnected-(IC301-I2Cm_SCL-Pad17)") (class "Default")
      (node (ref "IC301") (pin "17") (pinfunction "I2Cm_SCL_17") (pintype "passive"))
    )
    (net (code "129") (name "unconnected-(IC301-I2Cm_SDA-Pad16)") (class "Default")
      (node (ref "IC301") (pin "16") (pinfunction "I2Cm_SDA_16") (pintype "passive"))
    )
    (net (code "130") (name "unconnected-(IC301-I2Cs_IRQ-Pad10)") (class "Default")
      (node (ref "IC301") (pin "10") (pinfunction "I2Cs_IRQ_10") (pintype "passive"))
    )
    (net (code "131") (name "unconnected-(IC301-I2Cs_SCL-Pad9)") (class "Default")
      (node (ref "IC301") (pin "9") (pinfunction "I2Cs_SCL_9") (pintype "passive"))
    )
    (net (code "132") (name "unconnected-(IC301-I2Cs_SDA-Pad8)") (class "Default")
      (node (ref "IC301") (pin "8") (pinfunction "I2Cs_SDA_8") (pintype "passive"))
    )
    (net (code "133") (name "unconnected-(IC301-VBUS-Pad32)") (class "Default")
      (node (ref "IC301") (pin "32") (pinfunction "VBUS_32") (pintype "passive"))
    )
    (net (code "134") (name "unconnected-(IC301-VBUS-Pad33)") (class "Default")
      (node (ref "IC301") (pin "33") (pinfunction "VBUS_33") (pintype "passive"))
    )
    (net (code "135") (name "unconnected-(IC302-ADCIN1-Pad2)") (class "Default")
      (node (ref "IC302") (pin "2") (pinfunction "ADCIN1_2") (pintype "passive"))
    )
    (net (code "136") (name "unconnected-(IC302-ADCIN2-Pad3)") (class "Default")
      (node (ref "IC302") (pin "3") (pinfunction "ADCIN2_3") (pintype "passive"))
    )
    (net (code "137") (name "unconnected-(IC302-I2Cm_IRQ-Pad18)") (class "Default")
      (node (ref "IC302") (pin "18") (pinfunction "I2Cm_IRQ_18") (pintype "passive"))
    )
    (net (code "138") (name "unconnected-(IC302-I2Cm_SCL-Pad17)") (class "Default")
      (node (ref "IC302") (pin "17") (pinfunction "I2Cm_SCL_17") (pintype "passive"))
    )
    (net (code "139") (name "unconnected-(IC302-I2Cm_SDA-Pad16)") (class "Default")
      (node (ref "IC302") (pin "16") (pinfunction "I2Cm_SDA_16") (pintype "passive"))
    )
    (net (code "140") (name "unconnected-(IC302-I2Cs_IRQ-Pad10)") (class "Default")
      (node (ref "IC302") (pin "10") (pinfunction "I2Cs_IRQ_10") (pintype "passive"))
    )
    (net (code "141") (name "unconnected-(IC302-I2Cs_SCL-Pad9)") (class "Default")
      (node (ref "IC302") (pin "9") (pinfunction "I2Cs_SCL_9") (pintype "passive"))
    )
    (net (code "142") (name "unconnected-(IC302-I2Cs_SDA-Pad8)") (class "Default")
      (node (ref "IC302") (pin "8") (pinfunction "I2Cs_SDA_8") (pintype "passive"))
    )
    (net (code "143") (name "unconnected-(IC302-VBUS-Pad32)") (class "Default")
      (node (ref "IC302") (pin "32") (pinfunction "VBUS_32") (pintype "passive"))
    )
    (net (code "144") (name "unconnected-(IC302-VBUS-Pad33)") (class "Default")
      (node (ref "IC302") (pin "33") (pinfunction "VBUS_33") (pintype "passive"))
    )
    (net (code "145") (name "unconnected-(IC303-ADCIN1-Pad2)") (class "Default")
      (node (ref "IC303") (pin "2") (pinfunction "ADCIN1_2") (pintype "passive"))
    )
    (net (code "146") (name "unconnected-(IC303-ADCIN2-Pad3)") (class "Default")
      (node (ref "IC303") (pin "3") (pinfunction "ADCIN2_3") (pintype "passive"))
    )
    (net (code "147") (name "unconnected-(IC303-I2Cm_IRQ-Pad18)") (class "Default")
      (node (ref "IC303") (pin "18") (pinfunction "I2Cm_IRQ_18") (pintype "passive"))
    )
    (net (code "148") (name "unconnected-(IC303-I2Cm_SCL-Pad17)") (class "Default")
      (node (ref "IC303") (pin "17") (pinfunction "I2Cm_SCL_17") (pintype "passive"))
    )
    (net (code "149") (name "unconnected-(IC303-I2Cm_SDA-Pad16)") (class "Default")
      (node (ref "IC303") (pin "16") (pinfunction "I2Cm_SDA_16") (pintype "passive"))
    )
    (net (code "150") (name "unconnected-(IC303-I2Cs_IRQ-Pad10)") (class "Default")
      (node (ref "IC303") (pin "10") (pinfunction "I2Cs_IRQ_10") (pintype "passive"))
    )
    (net (code "151") (name "unconnected-(IC303-I2Cs_SCL-Pad9)") (class "Default")
      (node (ref "IC303") (pin "9") (pinfunction "I2Cs_SCL_9") (pintype "passive"))
    )
    (net (code "152") (name "unconnected-(IC303-I2Cs_SDA-Pad8)") (class "Default")
      (node (ref "IC303") (pin "8") (pinfunction "I2Cs_SDA_8") (pintype "passive"))
    )
    (net (code "153") (name "unconnected-(IC303-VBUS-Pad32)") (class "Default")
      (node (ref "IC303") (pin "32") (pinfunction "VBUS_32") (pintype "passive"))
    )
    (net (code "154") (name "unconnected-(IC303-VBUS-Pad33)") (class "Default")
      (node (ref "IC303") (pin "33") (pinfunction "VBUS_33") (pintype "passive"))
    )
    (net (code "155") (name "unconnected-(IC304-ADCIN1-Pad2)") (class "Default")
      (node (ref "IC304") (pin "2") (pinfunction "ADCIN1_2") (pintype "passive"))
    )
    (net (code "156") (name "unconnected-(IC304-ADCIN2-Pad3)") (class "Default")
      (node (ref "IC304") (pin "3") (pinfunction "ADCIN2_3") (pintype "passive"))
    )
    (net (code "157") (name "unconnected-(IC304-I2Cm_IRQ-Pad18)") (class "Default")
      (node (ref "IC304") (pin "18") (pinfunction "I2Cm_IRQ_18") (pintype "passive"))
    )
    (net (code "158") (name "unconnected-(IC304-I2Cm_SCL-Pad17)") (class "Default")
      (node (ref "IC304") (pin "17") (pinfunction "I2Cm_SCL_17") (pintype "passive"))
    )
    (net (code "159") (name "unconnected-(IC304-I2Cm_SDA-Pad16)") (class "Default")
      (node (ref "IC304") (pin "16") (pinfunction "I2Cm_SDA_16") (pintype "passive"))
    )
    (net (code "160") (name "unconnected-(IC304-I2Cs_IRQ-Pad10)") (class "Default")
      (node (ref "IC304") (pin "10") (pinfunction "I2Cs_IRQ_10") (pintype "passive"))
    )
    (net (code "161") (name "unconnected-(IC304-I2Cs_SCL-Pad9)") (class "Default")
      (node (ref "IC304") (pin "9") (pinfunction "I2Cs_SCL_9") (pintype "passive"))
    )
    (net (code "162") (name "unconnected-(IC304-I2Cs_SDA-Pad8)") (class "Default")
      (node (ref "IC304") (pin "8") (pinfunction "I2Cs_SDA_8") (pintype "passive"))
    )
    (net (code "163") (name "unconnected-(IC304-VBUS-Pad32)") (class "Default")
      (node (ref "IC304") (pin "32") (pinfunction "VBUS_32") (pintype "passive"))
    )
    (net (code "164") (name "unconnected-(IC304-VBUS-Pad33)") (class "Default")
      (node (ref "IC304") (pin "33") (pinfunction "VBUS_33") (pintype "passive"))
    )
    (net (code "165") (name "unconnected-(IC305-ADCIN1-Pad2)") (class "Default")
      (node (ref "IC305") (pin "2") (pinfunction "ADCIN1_2") (pintype "passive"))
    )
    (net (code "166") (name "unconnected-(IC305-ADCIN2-Pad3)") (class "Default")
      (node (ref "IC305") (pin "3") (pinfunction "ADCIN2_3") (pintype "passive"))
    )
    (net (code "167") (name "unconnected-(IC305-I2Cm_IRQ-Pad18)") (class "Default")
      (node (ref "IC305") (pin "18") (pinfunction "I2Cm_IRQ_18") (pintype "passive"))
    )
    (net (code "168") (name "unconnected-(IC305-I2Cm_SCL-Pad17)") (class "Default")
      (node (ref "IC305") (pin "17") (pinfunction "I2Cm_SCL_17") (pintype "passive"))
    )
    (net (code "169") (name "unconnected-(IC305-I2Cm_SDA-Pad16)") (class "Default")
      (node (ref "IC305") (pin "16") (pinfunction "I2Cm_SDA_16") (pintype "passive"))
    )
    (net (code "170") (name "unconnected-(IC305-I2Cs_IRQ-Pad10)") (class "Default")
      (node (ref "IC305") (pin "10") (pinfunction "I2Cs_IRQ_10") (pintype "passive"))
    )
    (net (code "171") (name "unconnected-(IC305-I2Cs_SCL-Pad9)") (class "Default")
      (node (ref "IC305") (pin "9") (pinfunction "I2Cs_SCL_9") (pintype "passive"))
    )
    (net (code "172") (name "unconnected-(IC305-I2Cs_SDA-Pad8)") (class "Default")
      (node (ref "IC305") (pin "8") (pinfunction "I2Cs_SDA_8") (pintype "passive"))
    )
    (net (code "173") (name "unconnected-(IC305-VBUS-Pad32)") (class "Default")
      (node (ref "IC305") (pin "32") (pinfunction "VBUS_32") (pintype "passive"))
    )
    (net (code "174") (name "unconnected-(IC305-VBUS-Pad33)") (class "Default")
      (node (ref "IC305") (pin "33") (pinfunction "VBUS_33") (pintype "passive"))
    )
    (net (code "175") (name "unconnected-(IC306-ADCIN1-Pad2)") (class "Default")
      (node (ref "IC306") (pin "2") (pinfunction "ADCIN1_2") (pintype "passive"))
    )
    (net (code "176") (name "unconnected-(IC306-ADCIN2-Pad3)") (class "Default")
      (node (ref "IC306") (pin "3") (pinfunction "ADCIN2_3") (pintype "passive"))
    )
    (net (code "177") (name "unconnected-(IC306-I2Cm_IRQ-Pad18)") (class "Default")
      (node (ref "IC306") (pin "18") (pinfunction "I2Cm_IRQ_18") (pintype "passive"))
    )
    (net (code "178") (name "unconnected-(IC306-I2Cm_SCL-Pad17)") (class "Default")
      (node (ref "IC306") (pin "17") (pinfunction "I2Cm_SCL_17") (pintype "passive"))
    )
    (net (code "179") (name "unconnected-(IC306-I2Cm_SDA-Pad16)") (class "Default")
      (node (ref "IC306") (pin "16") (pinfunction "I2Cm_SDA_16") (pintype "passive"))
    )
    (net (code "180") (name "unconnected-(IC306-I2Cs_IRQ-Pad10)") (class "Default")
      (node (ref "IC306") (pin "10") (pinfunction "I2Cs_IRQ_10") (pintype "passive"))
    )
    (net (code "181") (name "unconnected-(IC306-I2Cs_SCL-Pad9)") (class "Default")
      (node (ref "IC306") (pin "9") (pinfunction "I2Cs_SCL_9") (pintype "passive"))
    )
    (net (code "182") (name "unconnected-(IC306-I2Cs_SDA-Pad8)") (class "Default")
      (node (ref "IC306") (pin "8") (pinfunction "I2Cs_SDA_8") (pintype "passive"))
    )
    (net (code "183") (name "unconnected-(IC306-VBUS-Pad32)") (class "Default")
      (node (ref "IC306") (pin "32") (pinfunction "VBUS_32") (pintype "passive"))
    )
    (net (code "184") (name "unconnected-(IC306-VBUS-Pad33)") (class "Default")
      (node (ref "IC306") (pin "33") (pinfunction "VBUS_33") (pintype "passive"))
    )
    (net (code "185") (name "unconnected-(IC307-ADCIN1-Pad2)") (class "Default")
      (node (ref "IC307") (pin "2") (pinfunction "ADCIN1_2") (pintype "passive"))
    )
    (net (code "186") (name "unconnected-(IC307-ADCIN2-Pad3)") (class "Default")
      (node (ref "IC307") (pin "3") (pinfunction "ADCIN2_3") (pintype "passive"))
    )
    (net (code "187") (name "unconnected-(IC307-I2Cm_IRQ-Pad18)") (class "Default")
      (node (ref "IC307") (pin "18") (pinfunction "I2Cm_IRQ_18") (pintype "passive"))
    )
    (net (code "188") (name "unconnected-(IC307-I2Cm_SCL-Pad17)") (class "Default")
      (node (ref "IC307") (pin "17") (pinfunction "I2Cm_SCL_17") (pintype "passive"))
    )
    (net (code "189") (name "unconnected-(IC307-I2Cm_SDA-Pad16)") (class "Default")
      (node (ref "IC307") (pin "16") (pinfunction "I2Cm_SDA_16") (pintype "passive"))
    )
    (net (code "190") (name "unconnected-(IC307-I2Cs_IRQ-Pad10)") (class "Default")
      (node (ref "IC307") (pin "10") (pinfunction "I2Cs_IRQ_10") (pintype "passive"))
    )
    (net (code "191") (name "unconnected-(IC307-I2Cs_SCL-Pad9)") (class "Default")
      (node (ref "IC307") (pin "9") (pinfunction "I2Cs_SCL_9") (pintype "passive"))
    )
    (net (code "192") (name "unconnected-(IC307-I2Cs_SDA-Pad8)") (class "Default")
      (node (ref "IC307") (pin "8") (pinfunction "I2Cs_SDA_8") (pintype "passive"))
    )
    (net (code "193") (name "unconnected-(IC307-VBUS-Pad32)") (class "Default")
      (node (ref "IC307") (pin "32") (pinfunction "VBUS_32") (pintype "passive"))
    )
    (net (code "194") (name "unconnected-(IC307-VBUS-Pad33)") (class "Default")
      (node (ref "IC307") (pin "33") (pinfunction "VBUS_33") (pintype "passive"))
    )
    (net (code "195") (name "unconnected-(IC308-ADCIN1-Pad2)") (class "Default")
      (node (ref "IC308") (pin "2") (pinfunction "ADCIN1_2") (pintype "passive"))
    )
    (net (code "196") (name "unconnected-(IC308-ADCIN2-Pad3)") (class "Default")
      (node (ref "IC308") (pin "3") (pinfunction "ADCIN2_3") (pintype "passive"))
    )
    (net (code "197") (name "unconnected-(IC308-I2Cm_IRQ-Pad18)") (class "Default")
      (node (ref "IC308") (pin "18") (pinfunction "I2Cm_IRQ_18") (pintype "passive"))
    )
    (net (code "198") (name "unconnected-(IC308-I2Cm_SCL-Pad17)") (class "Default")
      (node (ref "IC308") (pin "17") (pinfunction "I2Cm_SCL_17") (pintype "passive"))
    )
    (net (code "199") (name "unconnected-(IC308-I2Cm_SDA-Pad16)") (class "Default")
      (node (ref "IC308") (pin "16") (pinfunction "I2Cm_SDA_16") (pintype "passive"))
    )
    (net (code "200") (name "unconnected-(IC308-I2Cs_IRQ-Pad10)") (class "Default")
      (node (ref "IC308") (pin "10") (pinfunction "I2Cs_IRQ_10") (pintype "passive"))
    )
    (net (code "201") (name "unconnected-(IC308-I2Cs_SCL-Pad9)") (class "Default")
      (node (ref "IC308") (pin "9") (pinfunction "I2Cs_SCL_9") (pintype "passive"))
    )
    (net (code "202") (name "unconnected-(IC308-I2Cs_SDA-Pad8)") (class "Default")
      (node (ref "IC308") (pin "8") (pinfunction "I2Cs_SDA_8") (pintype "passive"))
    )
    (net (code "203") (name "unconnected-(IC308-VBUS-Pad32)") (class "Default")
      (node (ref "IC308") (pin "32") (pinfunction "VBUS_32") (pintype "passive"))
    )
    (net (code "204") (name "unconnected-(IC308-VBUS-Pad33)") (class "Default")
      (node (ref "IC308") (pin "33") (pinfunction "VBUS_33") (pintype "passive"))
    )
  )
)
